# Konekt_Dash_Pro.net
KiCad netlist of a schematic drawn in EAGLE
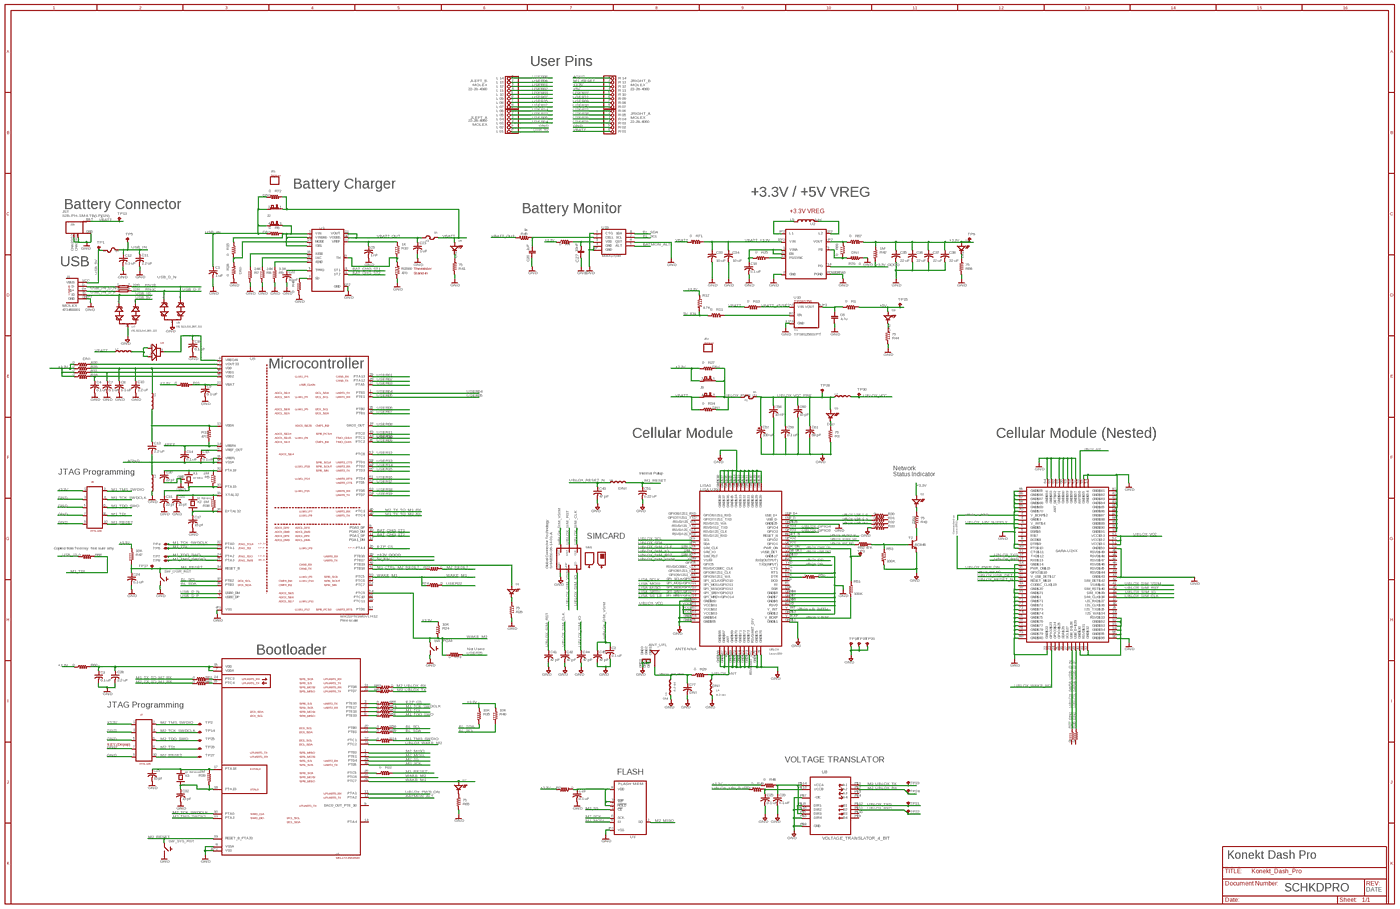
[diagram p0: schematic, sheet 1, overview]
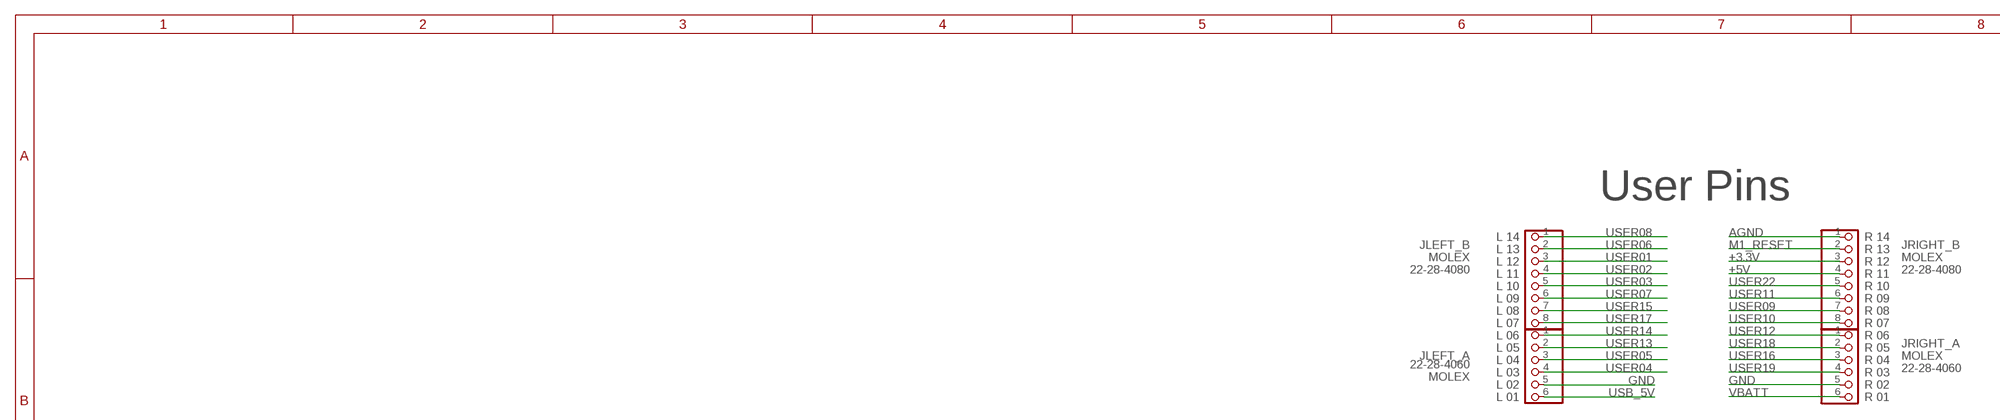
[diagram p1: schematic, sheet 1, part 1 of 4]
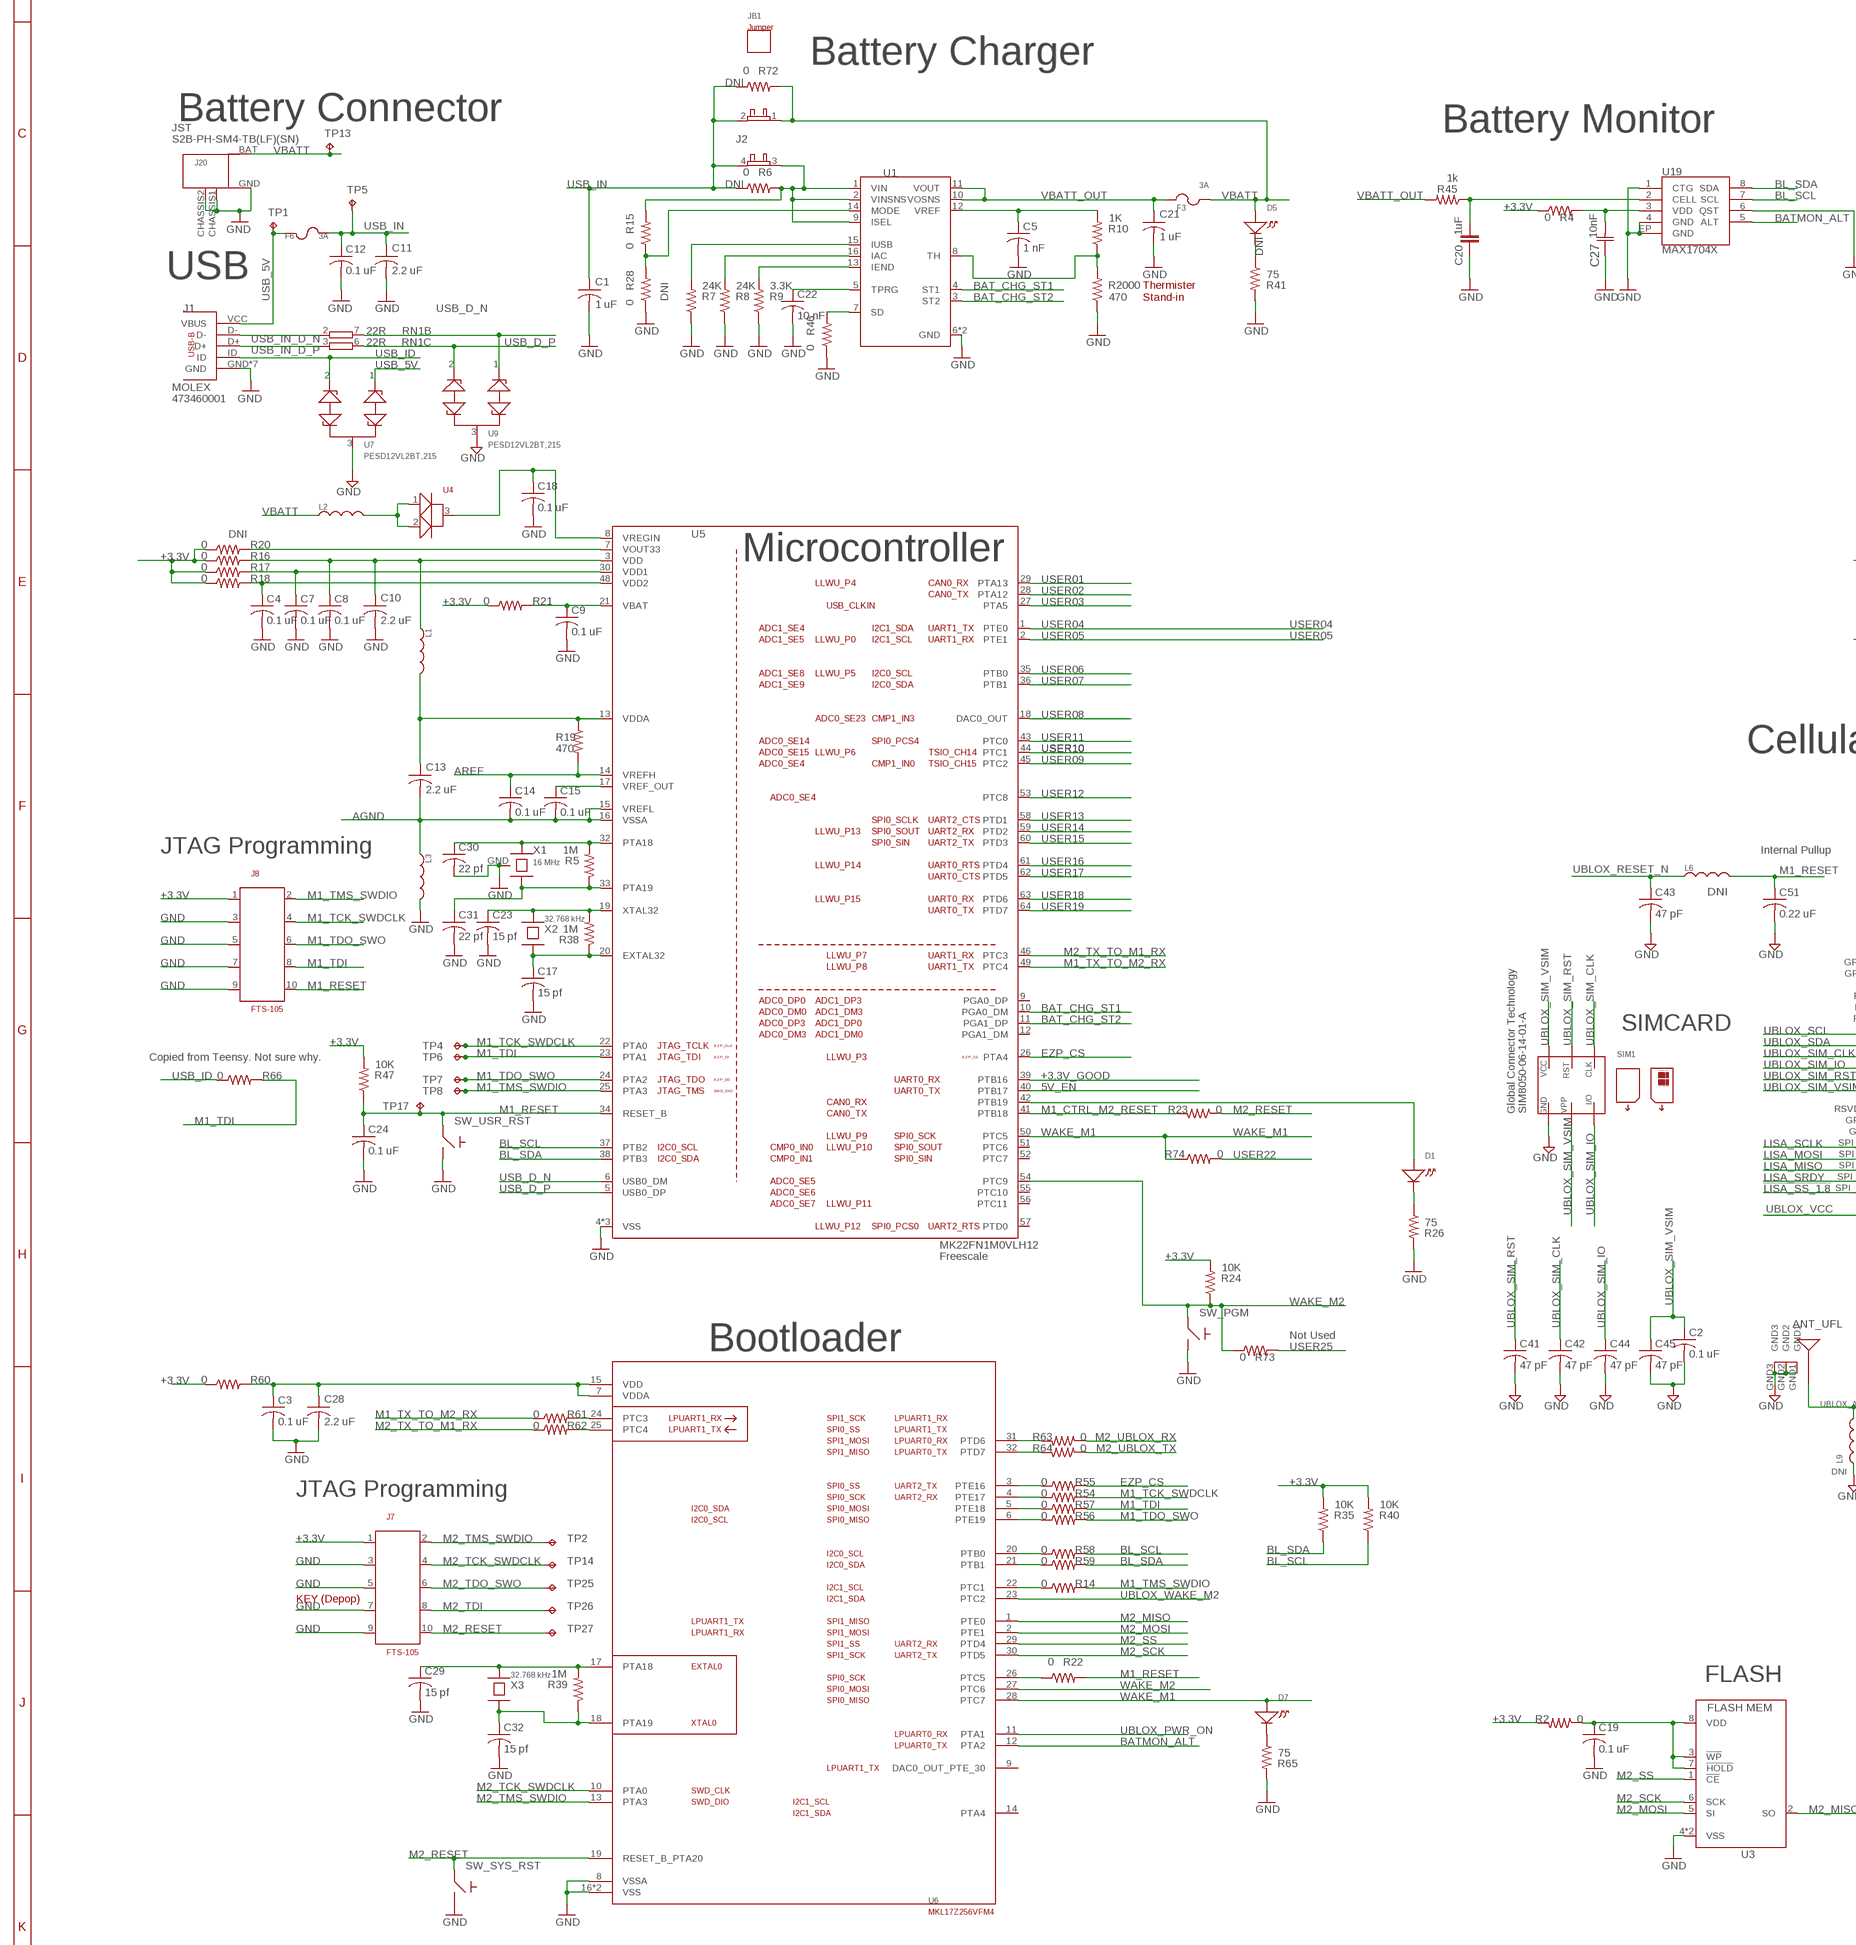
[diagram p2: schematic, sheet 1, part 2 of 4]
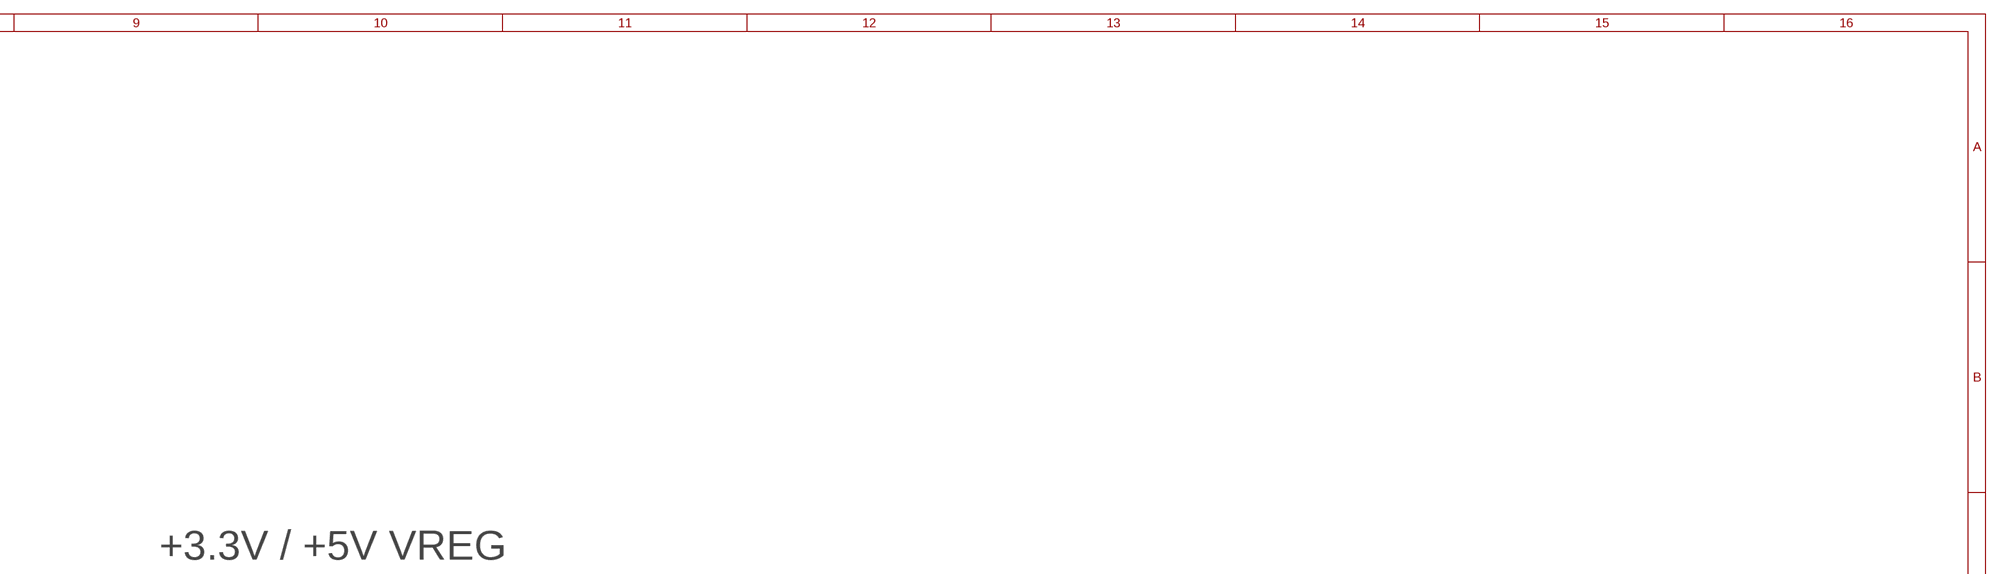
[diagram p3: schematic, sheet 1, part 3 of 4]
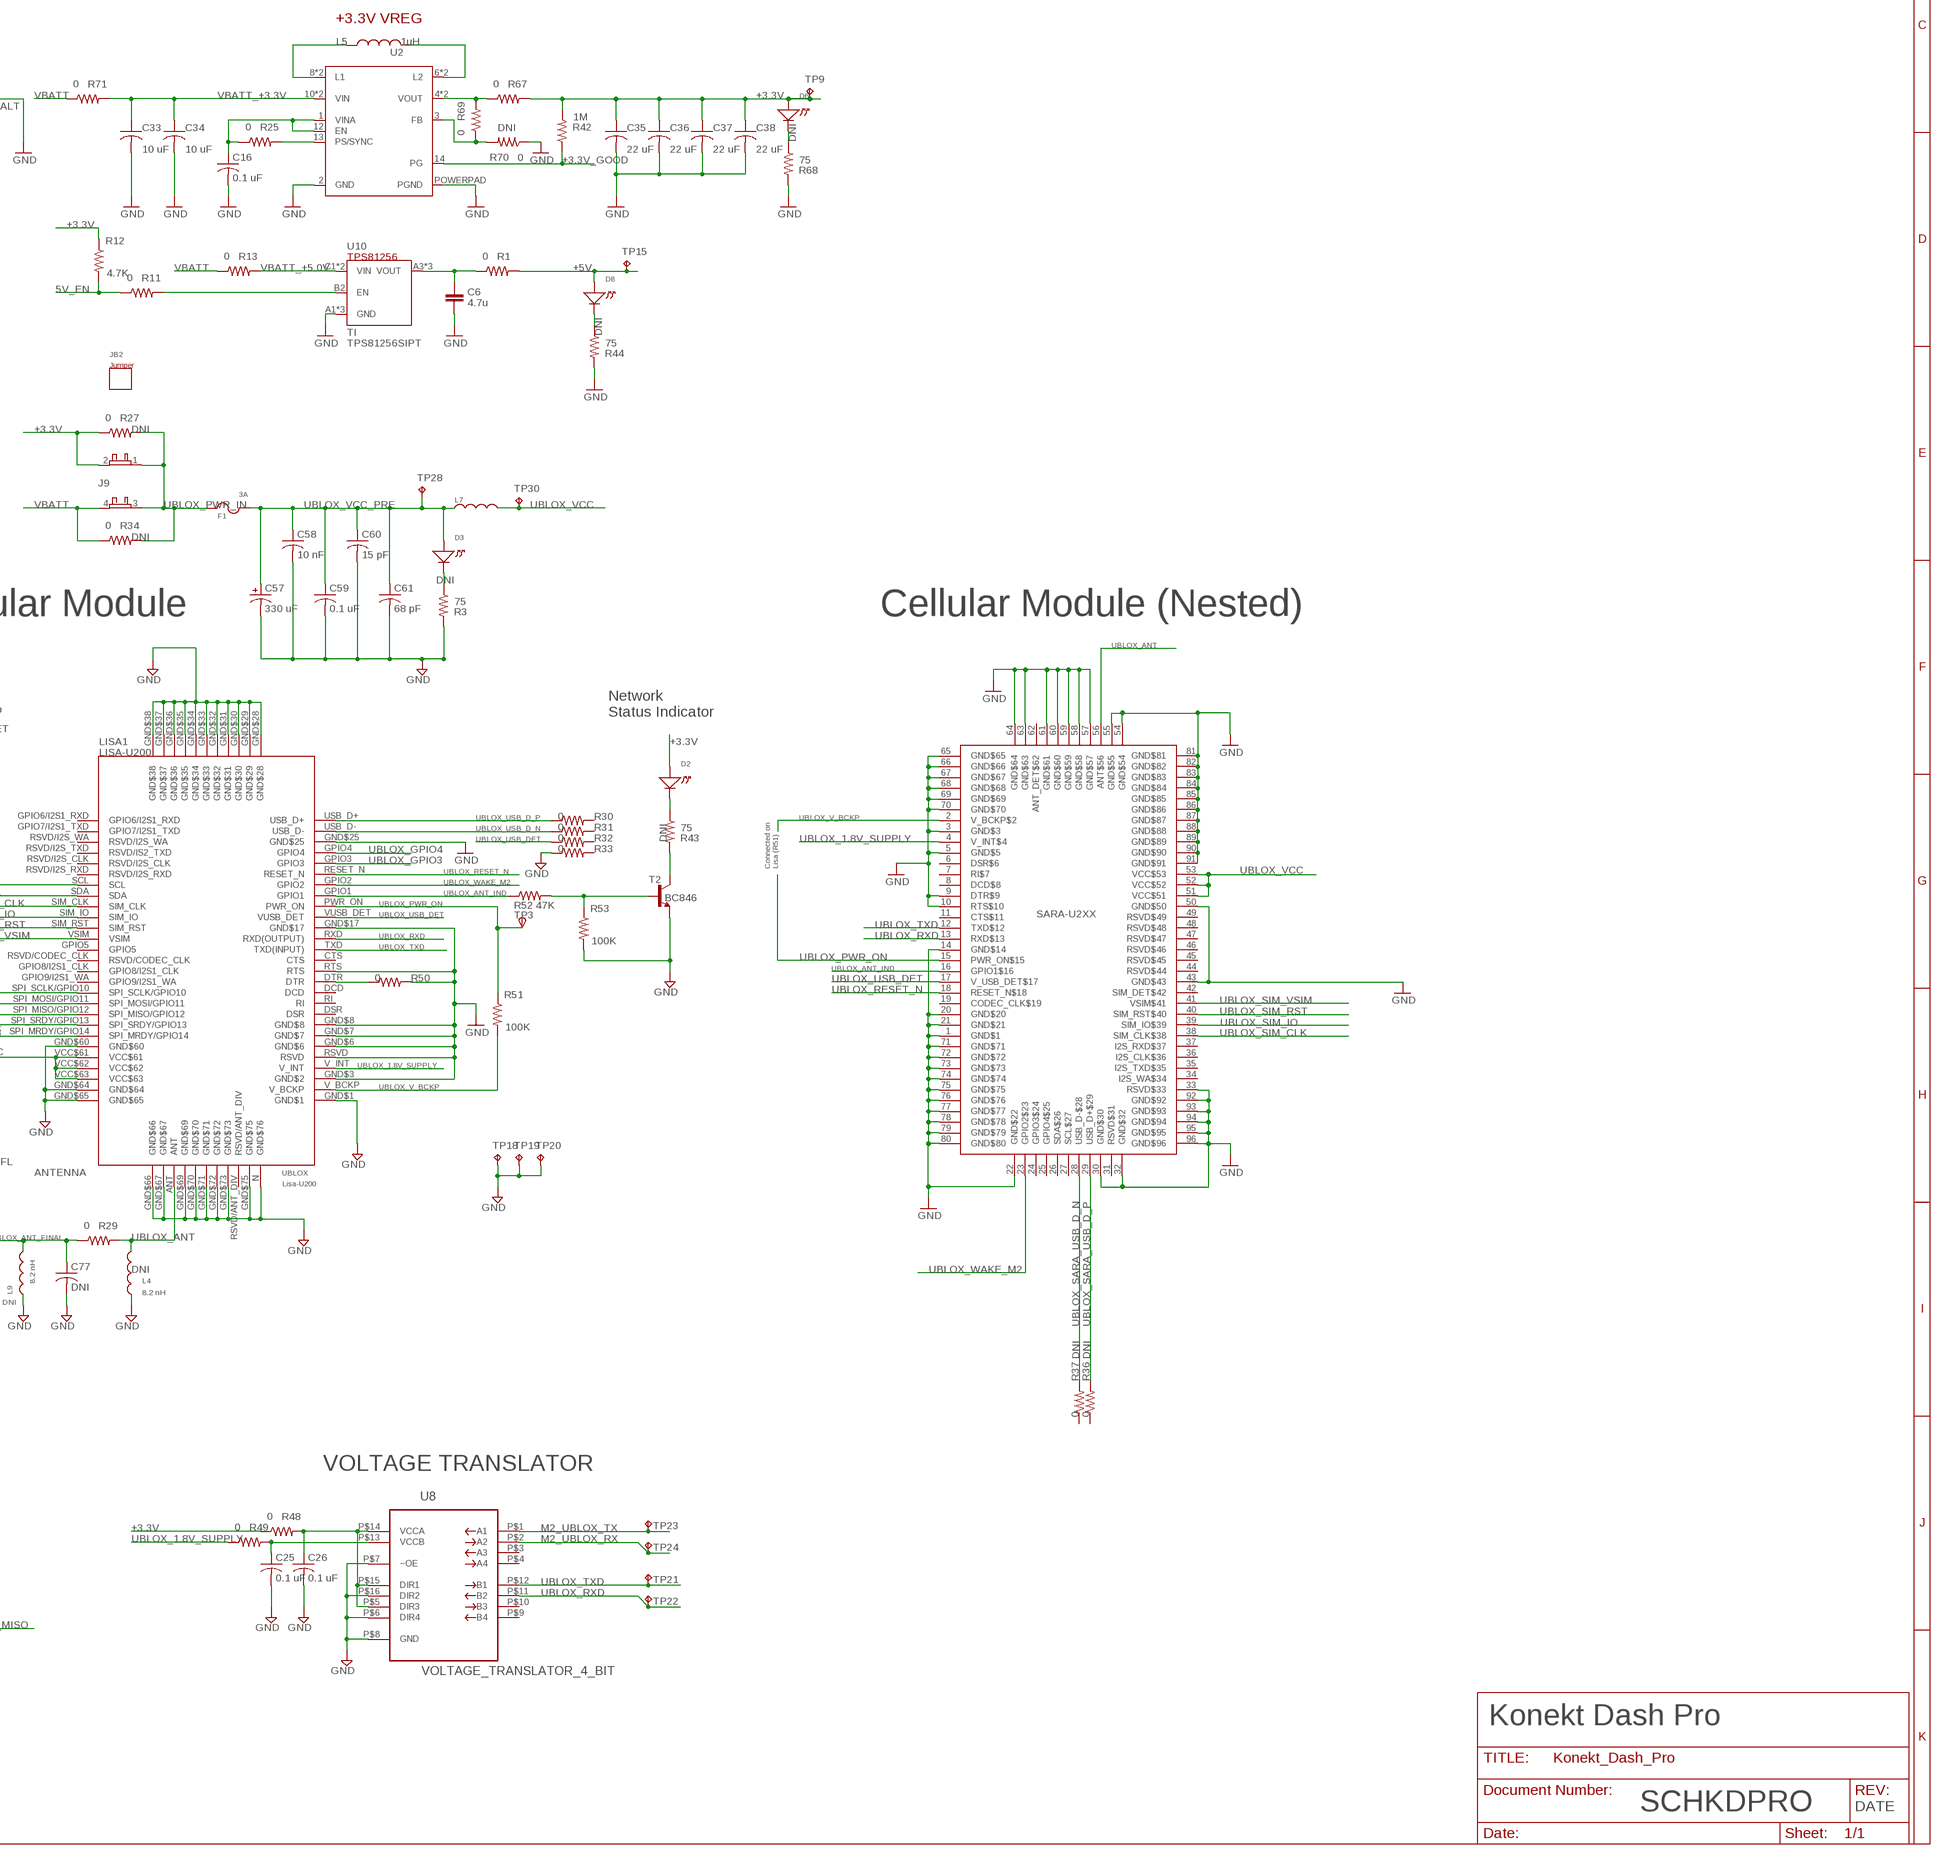
[diagram p4: schematic, sheet 1, part 4 of 4]

(export (version "E")
  (design (tool "Eeschema 10.0.6"))
  (components
    (comp (ref "ANT_UFL")
      (value "ANT-A-1JB")
      (footprint "eagle-import:UFL")
      (fields (field (name "MFG") "AMPHENOL") (field (name "PARTNUM") "A-1JB"))
      (libsource (lib "eagle-import") (part "ANT-A-1JB"))
    )
    (comp (ref "C1")
      (value "1 uF")
      (footprint "eagle-import:C0603")
      (fields (field (name "MFG") "MURATA") (field (name "MPN") "GRM188R71C105KA12D"))
      (libsource (lib "eagle-import") (part "resistor_C-USC0603"))
    )
    (comp (ref "C2")
      (value "0.1 uF")
      (footprint "eagle-import:C0402")
      (fields (field (name "MFG") "MURATA") (field (name "MPN") "GRM155R61C104KA88D"))
      (libsource (lib "eagle-import") (part "C-USC0402"))
    )
    (comp (ref "C3")
      (value "0.1 uF")
      (footprint "eagle-import:C0402")
      (fields (field (name "MFG") "MURATA") (field (name "MPN") "GRM155R61C104KA88D"))
      (libsource (lib "eagle-import") (part "C-USC0402"))
    )
    (comp (ref "C4")
      (value "0.1 uF")
      (footprint "eagle-import:C0402")
      (fields (field (name "MFG") "MURATA") (field (name "MPN") "GRM155R61C104KA88D"))
      (libsource (lib "eagle-import") (part "C-USC0402"))
    )
    (comp (ref "C5")
      (value "1 nF")
      (footprint "eagle-import:C0402")
      (fields (field (name "MFG") "MURATA") (field (name "MPN") "GRM319R71H102KA01D"))
      (libsource (lib "eagle-import") (part "resistor_C-USC0402"))
    )
    (comp (ref "C6")
      (value "4.7u")
      (footprint "eagle-import:C0603-ROUND")
      (fields (field (name "MFG") "MURATA") (field (name "MPN") "GRM188R61C475KAAJD"))
      (libsource (lib "eagle-import") (part "C-EU0603-RND"))
    )
    (comp (ref "C7")
      (value "0.1 uF")
      (footprint "eagle-import:C0402")
      (fields (field (name "MFG") "MURATA") (field (name "MPN") "GRM155R61C104KA88D"))
      (libsource (lib "eagle-import") (part "C-USC0402"))
    )
    (comp (ref "C8")
      (value "0.1 uF")
      (footprint "eagle-import:C0402")
      (fields (field (name "MFG") "MURATA") (field (name "MPN") "GRM155R61C104KA88D"))
      (libsource (lib "eagle-import") (part "C-USC0402"))
    )
    (comp (ref "C9")
      (value "0.1 uF")
      (footprint "eagle-import:C0402")
      (fields (field (name "MFG") "MURATA") (field (name "MPN") "GRM155R61C104KA88D"))
      (libsource (lib "eagle-import") (part "C-USC0402"))
    )
    (comp (ref "C10")
      (value "2.2 uF")
      (footprint "eagle-import:C0603")
      (fields (field (name "MFG") "SAMSUNG") (field (name "MPN") "CL10A225MQ8NNNC"))
      (libsource (lib "eagle-import") (part "resistor_C-USC0603"))
    )
    (comp (ref "C11")
      (value "2.2 uF")
      (footprint "eagle-import:C0603")
      (fields (field (name "MFG") "SAMSUNG") (field (name "MPN") "CL10A225MQ8NNNC"))
      (libsource (lib "eagle-import") (part "resistor_C-USC0603"))
    )
    (comp (ref "C12")
      (value "0.1 uF")
      (footprint "eagle-import:C0603")
      (fields (field (name "MFG") "AVX") (field (name "MPN") "0603YC104KAT2A"))
      (libsource (lib "eagle-import") (part "resistor_C-USC0603"))
    )
    (comp (ref "C13")
      (value "2.2 uF")
      (footprint "eagle-import:C0603")
      (fields (field (name "MFG") "SAMSUNG") (field (name "MPN") "CL10A225MQ8NNNC"))
      (libsource (lib "eagle-import") (part "resistor_C-USC0603"))
    )
    (comp (ref "C14")
      (value "0.1 uF")
      (footprint "eagle-import:C0402")
      (fields (field (name "MFG") "MURATA") (field (name "MPN") "GRM155R61C104KA88D"))
      (libsource (lib "eagle-import") (part "C-USC0402"))
    )
    (comp (ref "C15")
      (value "0.1 uF")
      (footprint "eagle-import:C0402")
      (fields (field (name "MFG") "AVX/ELCO") (field (name "MPN") "GRM155R61C104KA88D"))
      (libsource (lib "eagle-import") (part "C-USC0402"))
    )
    (comp (ref "C16")
      (value "0.1 uF")
      (footprint "eagle-import:C0603")
      (fields (field (name "MFG") "AVX") (field (name "MPN") "0603YC104KAT2A"))
      (libsource (lib "eagle-import") (part "resistor_C-USC0603"))
    )
    (comp (ref "C17")
      (value "15 pf")
      (footprint "eagle-import:C0402")
      (fields (field (name "MFG") "AVX/ELCO") (field (name "MPN") "04025A150JAT2A"))
      (libsource (lib "eagle-import") (part "C-USC0402"))
    )
    (comp (ref "C18")
      (value "0.1 uF")
      (footprint "eagle-import:C0402")
      (fields (field (name "MFG") "MURATA") (field (name "MPN") "GRM155R61C104KA88D"))
      (libsource (lib "eagle-import") (part "C-USC0402"))
    )
    (comp (ref "C19")
      (value "0.1 uF")
      (footprint "eagle-import:C0402")
      (fields (field (name "MFG") "MURATA") (field (name "MPN") "GRM155R61C104KA88D"))
      (libsource (lib "eagle-import") (part "C-USC0402"))
    )
    (comp (ref "C20")
      (value "1uF")
      (footprint "eagle-import:0402-CAP")
      (description "Capacitor, 10%, 50V")
      (fields
        (field (name "MFG") "AVX")
        (field (name "MPN") "04026D105KAT2A")
        (field (name "TOLERANCE") "10%")
        (field (name "VOLTAGE") "50V")
      )
      (libsource (lib "eagle-import") (part "CAPACITOR0402"))
    )
    (comp (ref "C21")
      (value "1 uF")
      (footprint "eagle-import:C0603")
      (fields (field (name "MFG") "MURATA") (field (name "MPN") "GRM188R71C105KA12D"))
      (libsource (lib "eagle-import") (part "resistor_C-USC0603"))
    )
    (comp (ref "C22")
      (value "10 nF")
      (footprint "eagle-import:C0402")
      (fields (field (name "MFG") "MURATA") (field (name "MPN") "GRM155R71C103KA01D"))
      (libsource (lib "eagle-import") (part "resistor_C-USC0402"))
    )
    (comp (ref "C23")
      (value "15 pf")
      (footprint "eagle-import:C0402")
      (fields (field (name "MFG") "AVX/ELCO") (field (name "MPN") "04025A150JAT2A"))
      (libsource (lib "eagle-import") (part "C-USC0402"))
    )
    (comp (ref "C24")
      (value "0.1 uF")
      (footprint "eagle-import:C0402")
      (fields (field (name "MFG") "MURATA") (field (name "MPN") "GRM155R61C104KA88D"))
      (libsource (lib "eagle-import") (part "C-USC0402"))
    )
    (comp (ref "C25")
      (value "0.1 uF")
      (footprint "eagle-import:C0402")
      (fields (field (name "MFG") "MURATA") (field (name "MPN") "GRM155R61C104KA88D"))
      (libsource (lib "eagle-import") (part "C-USC0402"))
    )
    (comp (ref "C26")
      (value "0.1 uF")
      (footprint "eagle-import:C0402")
      (fields (field (name "MFG") "MURATA") (field (name "MPN") "GRM155R61C104KA88D"))
      (libsource (lib "eagle-import") (part "C-USC0402"))
    )
    (comp (ref "C27")
      (value "10nF")
      (footprint "eagle-import:CAPC1005X60N")
      (description "CAPACITOR, 0402")
      (fields (field (name "MPN") "GRM155R71E103KA01D") (field (name "TOLERANCE") "±10%"))
      (libsource (lib "eagle-import") (part "GRM155R71E103KA01D"))
    )
    (comp (ref "C28")
      (value "2.2 uF")
      (footprint "eagle-import:C0603")
      (fields (field (name "MFG") "SAMSUNG") (field (name "MPN") "CL10A225MQ8NNNC"))
      (libsource (lib "eagle-import") (part "resistor_C-USC0603"))
    )
    (comp (ref "C29")
      (value "15 pf")
      (footprint "eagle-import:C0402")
      (fields (field (name "MFG") "AVX/ELCO") (field (name "MPN") "04025A150JAT2A"))
      (libsource (lib "eagle-import") (part "C-USC0402"))
    )
    (comp (ref "C30")
      (value "22 pf")
      (footprint "eagle-import:C0402")
      (fields (field (name "MFG") "AVX/ELCO") (field (name "MPN") "04025A220JAT2A"))
      (libsource (lib "eagle-import") (part "C-USC0402"))
    )
    (comp (ref "C31")
      (value "22 pf")
      (footprint "eagle-import:C0402")
      (fields (field (name "MFG") "AVX/ELCO") (field (name "MPN") "04025A220JAT2A"))
      (libsource (lib "eagle-import") (part "C-USC0402"))
    )
    (comp (ref "C32")
      (value "15 pf")
      (footprint "eagle-import:C0402")
      (fields (field (name "MFG") "AVX/ELCO") (field (name "MPN") "04025A150JAT2A"))
      (libsource (lib "eagle-import") (part "C-USC0402"))
    )
    (comp (ref "C33")
      (value "10 uF")
      (footprint "eagle-import:C0603")
      (fields (field (name "MFG") "MURATA") (field (name "MPN") "GRM188R60J106ME84D"))
      (libsource (lib "eagle-import") (part "resistor_C-USC0603"))
    )
    (comp (ref "C34")
      (value "10 uF")
      (footprint "eagle-import:C0603")
      (fields (field (name "MFG") "MURATA") (field (name "MPN") "GRM188R60J106ME84D"))
      (libsource (lib "eagle-import") (part "resistor_C-USC0603"))
    )
    (comp (ref "C35")
      (value "22 uF")
      (footprint "eagle-import:C0603")
      (fields (field (name "MFG") "MURATA") (field (name "MPN") "GRM188R60J226MEA0D"))
      (libsource (lib "eagle-import") (part "resistor_C-USC0603"))
    )
    (comp (ref "C36")
      (value "22 uF")
      (footprint "eagle-import:C0603")
      (fields (field (name "MFG") "MURATA") (field (name "MPN") "GRM188R60J226MEA0D"))
      (libsource (lib "eagle-import") (part "resistor_C-USC0603"))
    )
    (comp (ref "C37")
      (value "22 uF")
      (footprint "eagle-import:C0603")
      (fields (field (name "MFG") "MURATA") (field (name "MPN") "GRM188R60J226MEA0D"))
      (libsource (lib "eagle-import") (part "resistor_C-USC0603"))
    )
    (comp (ref "C38")
      (value "22 uF")
      (footprint "eagle-import:C0603")
      (fields (field (name "MFG") "MURATA") (field (name "MPN") "GRM188R60J226MEA0D"))
      (libsource (lib "eagle-import") (part "resistor_C-USC0603"))
    )
    (comp (ref "C41")
      (value "47 pF")
      (footprint "eagle-import:C0402")
      (fields (field (name "MFG") "AVX") (field (name "MPN") "04025A470JAT2A"))
      (libsource (lib "eagle-import") (part "resistor_C-USC0402"))
    )
    (comp (ref "C42")
      (value "47 pF")
      (footprint "eagle-import:C0402")
      (fields (field (name "MFG") "AVX") (field (name "MPN") "04025A470JAT2A"))
      (libsource (lib "eagle-import") (part "resistor_C-USC0402"))
    )
    (comp (ref "C43")
      (value "47 pF")
      (footprint "eagle-import:C0402")
      (fields (field (name "MFG") "AVX") (field (name "MPN") "04025A470JAT2A"))
      (libsource (lib "eagle-import") (part "resistor_C-USC0402"))
    )
    (comp (ref "C44")
      (value "47 pF")
      (footprint "eagle-import:C0402")
      (fields (field (name "MFG") "AVX") (field (name "MPN") "04025A470JAT2A"))
      (libsource (lib "eagle-import") (part "resistor_C-USC0402"))
    )
    (comp (ref "C45")
      (value "47 pF")
      (footprint "eagle-import:C0402")
      (fields (field (name "MFG") "AVX") (field (name "MPN") "04025A470JAT2A"))
      (libsource (lib "eagle-import") (part "resistor_C-USC0402"))
    )
    (comp (ref "C51")
      (value "0.22 uF")
      (footprint "eagle-import:C0603")
      (fields (field (name "MFG") "AVX") (field (name "MPN") "0603YC224KAT2A"))
      (libsource (lib "eagle-import") (part "resistor_C-USC0603"))
    )
    (comp (ref "C57")
      (value "330 uF")
      (footprint "eagle-import:CAP_SMD_SIZE_D")
      (fields (field (name "MFG") "KEMET") (field (name "MPN") "T520D337M006ATE045"))
      (libsource (lib "eagle-import") (part "CAP_SMD_D_SIZED"))
    )
    (comp (ref "C58")
      (value "10 nF")
      (footprint "eagle-import:C0402")
      (fields (field (name "MFG") "MURATA") (field (name "MPN") "GRM155R71C103KA01D"))
      (libsource (lib "eagle-import") (part "resistor_C-USC0402"))
    )
    (comp (ref "C59")
      (value "0.1 uF")
      (footprint "eagle-import:C0603")
      (fields (field (name "MFG") "AVX") (field (name "MPN") "0603YC104KAT2A"))
      (libsource (lib "eagle-import") (part "resistor_C-USC0603"))
    )
    (comp (ref "C60")
      (value "15 pF")
      (footprint "eagle-import:C0402")
      (fields (field (name "MFG") "NIC") (field (name "MPN") "NMC0402NPO150J50TRPF"))
      (libsource (lib "eagle-import") (part "resistor_C-USC0402"))
    )
    (comp (ref "C61")
      (value "68 pF")
      (footprint "eagle-import:C0402")
      (fields (field (name "MFG") "MURATA") (field (name "MPN") "GRM1555C1H680JA01D"))
      (libsource (lib "eagle-import") (part "resistor_C-USC0402"))
    )
    (comp (ref "C77")
      (value "DNI")
      (footprint "eagle-import:C0402")
      (fields (field (name "MFG") "AVX"))
      (libsource (lib "eagle-import") (part "resistor_C-USC0402"))
    )
    (comp (ref "D1")
      (value "LED_0402_VLMW")
      (footprint "eagle-import:LED_0402_VISHAY_VLMW")
      (fields (field (name "MFG") "VISHAY") (field (name "MPN") "VLMW1500-GS08"))
      (libsource (lib "eagle-import") (part "LED_0402_VLMW"))
    )
    (comp (ref "D2")
      (value "LED_0402_VLMW")
      (footprint "eagle-import:LED_0402_VISHAY_VLMW")
      (fields (field (name "MFG") "VISHAY") (field (name "MPN") "VLMW1500-GS08"))
      (libsource (lib "eagle-import") (part "LED_0402_VLMW"))
    )
    (comp (ref "D3")
      (value "LED_0402_VLMW")
      (footprint "eagle-import:LED_0402_VISHAY_VLMW")
      (fields (field (name "MFG") "VISHAY") (field (name "MPN") "VLMW1500-GS08"))
      (libsource (lib "eagle-import") (part "LED_0402_VLMW"))
    )
    (comp (ref "D5")
      (value "LED_0402_VLMW")
      (footprint "eagle-import:LED_0402_VISHAY_VLMW")
      (fields (field (name "MFG") "VISHAY") (field (name "MPN") "VLMW1500-GS08"))
      (libsource (lib "eagle-import") (part "LED_0402_VLMW"))
    )
    (comp (ref "D6")
      (value "LED_0402_VLMW")
      (footprint "eagle-import:LED_0402_VISHAY_VLMW")
      (fields (field (name "MFG") "VISHAY") (field (name "MPN") "VLMW1500-GS08"))
      (libsource (lib "eagle-import") (part "LED_0402_VLMW"))
    )
    (comp (ref "D7")
      (value "LED_0402_VLMW")
      (footprint "eagle-import:LED_0402_VISHAY_VLMW")
      (fields (field (name "MFG") "VISHAY") (field (name "MPN") "VLMW1500-GS08"))
      (libsource (lib "eagle-import") (part "LED_0402_VLMW"))
    )
    (comp (ref "D8")
      (value "LED_0402_VLMW")
      (footprint "eagle-import:LED_0402_VISHAY_VLMW")
      (fields (field (name "MFG") "VISHAY") (field (name "MPN") "VLMW1500-GS08"))
      (libsource (lib "eagle-import") (part "LED_0402_VLMW"))
    )
    (comp (ref "F1")
      (value "3A")
      (footprint "eagle-import:R0603")
      (fields (field (name "MFG") "Bourns") (field (name "MPN") "SF-0603S300-2"))
      (libsource (lib "eagle-import") (part "FUSE_0603"))
    )
    (comp (ref "F3")
      (value "3A")
      (footprint "eagle-import:R0603")
      (fields (field (name "MFG") "Bourns") (field (name "MPN") "SF-0603S300-2"))
      (libsource (lib "eagle-import") (part "FUSE_0603"))
    )
    (comp (ref "F6")
      (value "3A")
      (footprint "eagle-import:R0603")
      (fields (field (name "MFG") "Bourns") (field (name "MPN") "SF-0603S300-2"))
      (libsource (lib "eagle-import") (part "FUSE_0603"))
    )
    (comp (ref "J1")
      (value "USB_MICRO_B_MOLEX_473460001")
      (footprint "eagle-import:USB_MICRO_MOLEX_473460001")
      (fields
        (field (name "MFG") "MOLEX")
        (field (name "PARTNUM") "473460001")
        (field (name "MPN") "473460001")
      )
      (libsource (lib "eagle-import") (part "USB_MICRO_B_MOLEX_473460001"))
    )
    (comp (ref "J2")
      (value "CON_JUMPER_1.27_2X2")
      (footprint "eagle-import:FCI_CON_1.27_2X2")
      (fields (field (name "MFG") "FCI") (field (name "MPN") "20021121-00004C4LF"))
      (libsource (lib "eagle-import") (part "CON_JUMPER_1.27_2X2"))
    )
    (comp (ref "J7")
      (value "FTS-105")
      (footprint "eagle-import:FTS-105")
      (fields (field (name "MFG") "SAMTEC") (field (name "PARTNUM") "FTS-105-01-F-DV"))
      (libsource (lib "eagle-import") (part "FTS-105"))
    )
    (comp (ref "J8")
      (value "FTS-105")
      (footprint "eagle-import:FTS-105")
      (fields (field (name "MFG") "SAMTEC") (field (name "PARTNUM") "FTS-105-01-F-DV"))
      (libsource (lib "eagle-import") (part "FTS-105"))
    )
    (comp (ref "J9")
      (value "CON_JUMPER_1.27_2X2")
      (footprint "eagle-import:FCI_CON_1.27_2X2")
      (fields (field (name "MFG") "FCI") (field (name "MPN") "20021121-00004C4LF"))
      (libsource (lib "eagle-import") (part "CON_JUMPER_1.27_2X2"))
    )
    (comp (ref "J20")
      (value "BAT_TERM")
      (footprint "eagle-import:JST-PH-2")
      (fields
        (field (name "MFG") "JST")
        (field (name "PARTNUM") "S2B-PH-SM4-TB(LF)(SN)")
        (field (name "MFG_1") "JST")
        (field (name "MPN") "S2B-PH-SM4-TB(LF)(SN)")
        (field (name "PARTNUM_1") "S2B-PH-SM4-TB(LF)(SN)")
      )
      (libsource (lib "eagle-import") (part "BAT_TERM"))
    )
    (comp (ref "JB1")
      (value "JUMPER_1.27MM")
      (footprint "eagle-import:NOTHING")
      (fields (field (name "MFG") "HARWIN") (field (name "MPN") "M50-1920005"))
      (libsource (lib "eagle-import") (part "JUMPER_1.27MM"))
    )
    (comp (ref "JB2")
      (value "JUMPER_1.27MM")
      (footprint "eagle-import:NOTHING")
      (fields (field (name "MFG") "HARWIN") (field (name "MPN") "M50-1920005"))
      (libsource (lib "eagle-import") (part "JUMPER_1.27MM"))
    )
    (comp (ref "JLEFT_A")
      (value "PINHD-1X6")
      (footprint "eagle-import:1X06")
      (fields (field (name "MFG") "MOLEX") (field (name "MPN") "22-28-4060"))
      (libsource (lib "eagle-import") (part "PINHD-1X6"))
    )
    (comp (ref "JLEFT_B")
      (value "HEADER_0.1_IN_8_POS")
      (footprint "eagle-import:HEADER_0.1_8_POS")
      (fields
        (field (name "MFG") "Adam Tech")
        (field (name "MPN") "RS1-08-G-.561-A11596")
        (field (name "MFG_1") "MOLEX")
        (field (name "MPN_1") "22-28-4080")
      )
      (libsource (lib "eagle-import") (part "HEADER_0.1_IN_8_POS"))
    )
    (comp (ref "JRIGHT_A")
      (value "PINHD-1X6")
      (footprint "eagle-import:1X06")
      (fields (field (name "MFG") "MOLEX") (field (name "MPN") "22-28-4060"))
      (libsource (lib "eagle-import") (part "PINHD-1X6"))
    )
    (comp (ref "JRIGHT_B")
      (value "HEADER_0.1_IN_8_POS")
      (footprint "eagle-import:HEADER_0.1_8_POS")
      (fields
        (field (name "MFG") "Adam Tech")
        (field (name "MPN") "RS1-08-G-.561-A11596")
        (field (name "MFG_1") "MOLEX")
        (field (name "MPN_1") "22-28-4080")
      )
      (libsource (lib "eagle-import") (part "HEADER_0.1_IN_8_POS"))
    )
    (comp (ref "L1")
      (value "INDUCTOR_0603")
      (footprint "eagle-import:R0603$1")
      (fields (field (name "MFG") "Murata") (field (name "MPN") "BLM18AG121SN1D"))
      (libsource (lib "eagle-import") (part "INDUCTOR_0603"))
    )
    (comp (ref "L2")
      (value "INDUCTOR_0603")
      (footprint "eagle-import:R0603$1")
      (fields (field (name "MFG") "TDK") (field (name "MPN") "MPZ1608S221A"))
      (libsource (lib "eagle-import") (part "INDUCTOR_0603"))
    )
    (comp (ref "L3")
      (value "INDUCTOR_0603")
      (footprint "eagle-import:R0603$1")
      (fields (field (name "MFG") "Murata") (field (name "MPN") "BLM18AG121SN1D"))
      (libsource (lib "eagle-import") (part "INDUCTOR_0603"))
    )
    (comp (ref "L4")
      (value "INDUCTOR_0402")
      (footprint "eagle-import:R0402")
      (fields (field (name "MFG") "TDK") (field (name "MPN") "DNI") (field (name "VAL") "8.2 nH"))
      (libsource (lib "eagle-import") (part "INDUCTOR_0402"))
    )
    (comp (ref "L5")
      (value "1uH")
      (footprint "eagle-import:COILCRAFT_XFL4020")
      (fields (field (name "MFG") "COILCRAFT") (field (name "MPN") "XFL4020-102MEC"))
      (libsource (lib "eagle-import") (part "INDUCTOR_1UH_XFL4020-102MEC"))
    )
    (comp (ref "L6")
      (value "INDUCTOR_0603")
      (footprint "eagle-import:R0603$1")
      (fields (field (name "MFG") "TDK") (field (name "MPN") "DNI"))
      (libsource (lib "eagle-import") (part "INDUCTOR_0603"))
    )
    (comp (ref "L7")
      (value "INDUCTOR_0603")
      (footprint "eagle-import:R0603$1")
      (fields (field (name "MFG") "MURATA") (field (name "MPN") "BLM18EG221SN1D"))
      (libsource (lib "eagle-import") (part "INDUCTOR_0603"))
    )
    (comp (ref "L9")
      (value "INDUCTOR_0402")
      (footprint "eagle-import:R0402")
      (fields (field (name "MFG") "TDK") (field (name "MPN") "DNI") (field (name "VAL") "8.2 nH"))
      (libsource (lib "eagle-import") (part "INDUCTOR_0402"))
    )
    (comp (ref "LISA1")
      (value "LISA-U200")
      (footprint "eagle-import:76PIN_LCC")
      (fields
        (field (name "MFG") "UBLOX")
        (field (name "MPN") "LISA-U200-02S")
        (field (name "PARTNUM") "Lisa-U200")
      )
      (libsource (lib "eagle-import") (part "LISA-U200"))
    )
    (comp (ref "R1")
      (value "0")
      (footprint "eagle-import:0402-RES")
      (description "Resistor, 1%, 0.125W")
      (fields
        (field (name "MANUFACTURER") "Panasonic")
        (field (name "MFG") "PANASONIC")
        (field (name "MPN") "ERJ-2GE0R00X")
      )
      (libsource (lib "eagle-import") (part "RESISTOR0402-RES"))
    )
    (comp (ref "R2")
      (value "0")
      (footprint "eagle-import:0402-RES")
      (description "Resistor, 1%, 0.125W")
      (fields
        (field (name "MANUFACTURER") "Panasonic")
        (field (name "MFG") "PANASONIC")
        (field (name "MPN") "ERJ-2GE0R00X")
      )
      (libsource (lib "eagle-import") (part "RESISTOR0402-RES"))
    )
    (comp (ref "R3")
      (value "75")
      (footprint "eagle-import:0402-RES")
      (description "Resistor, 1%, 0.125W")
      (fields
        (field (name "MANUFACTURER") "Panasonic")
        (field (name "MFG") "PANASONIC")
        (field (name "MPN") "DNI")
      )
      (libsource (lib "eagle-import") (part "RESISTOR0402-RES"))
    )
    (comp (ref "R4")
      (value "0")
      (footprint "eagle-import:0402-RES")
      (description "Resistor, 1%, 0.125W")
      (fields
        (field (name "MANUFACTURER") "Panasonic")
        (field (name "MFG") "PANASONIC")
        (field (name "MPN") "ERJ-2GE0R00X")
      )
      (libsource (lib "eagle-import") (part "RESISTOR0402-RES"))
    )
    (comp (ref "R5")
      (value "1M")
      (footprint "eagle-import:0402-RES")
      (description "Resistor, 1%, 0.125W")
      (fields
        (field (name "MANUFACTURER") "Yaego")
        (field (name "MFG") "YAEGO")
        (field (name "MPN") "RC0402JR-071ML")
      )
      (libsource (lib "eagle-import") (part "RESISTOR0402-RES"))
    )
    (comp (ref "R6")
      (value "0")
      (footprint "eagle-import:0402-RES")
      (description "Resistor, 1%, 0.125W")
      (fields
        (field (name "MANUFACTURER") "Panasonic")
        (field (name "MFG") "PANASONIC")
        (field (name "MPN") "DNI")
      )
      (libsource (lib "eagle-import") (part "RESISTOR0402-RES"))
    )
    (comp (ref "R7")
      (value "24K")
      (footprint "eagle-import:0402-RES")
      (description "Resistor, 1%, 0.125W")
      (fields
        (field (name "MANUFACTURER") "Yaego")
        (field (name "MFG") "YAEGO")
        (field (name "MPN") "RC0402JR-0724KL")
      )
      (libsource (lib "eagle-import") (part "RESISTOR0402-RES"))
    )
    (comp (ref "R8")
      (value "24K")
      (footprint "eagle-import:0402-RES")
      (description "Resistor, 1%, 0.125W")
      (fields
        (field (name "MANUFACTURER") "Yaego")
        (field (name "MFG") "YAEGO")
        (field (name "MPN") "RC0402JR-0724KL")
      )
      (libsource (lib "eagle-import") (part "RESISTOR0402-RES"))
    )
    (comp (ref "R9")
      (value "3.3K")
      (footprint "eagle-import:0402-RES")
      (description "Resistor, 1%, 0.125W")
      (fields
        (field (name "MANUFACTURER") "Yaego")
        (field (name "MFG") "YAEGO")
        (field (name "MPN") "RC0402JR-073K3L")
      )
      (libsource (lib "eagle-import") (part "RESISTOR0402-RES"))
    )
    (comp (ref "R10")
      (value "1K")
      (footprint "eagle-import:0402-RES")
      (description "Resistor, 1%, 0.125W")
      (fields
        (field (name "MANUFACTURER") "Yaego")
        (field (name "MFG") "YAEGO")
        (field (name "MPN") "RC0402JR-071KL")
      )
      (libsource (lib "eagle-import") (part "RESISTOR0402-RES"))
    )
    (comp (ref "R11")
      (value "0")
      (footprint "eagle-import:0402-RES")
      (description "Resistor, 1%, 0.125W")
      (fields
        (field (name "MANUFACTURER") "Panasonic")
        (field (name "MFG") "PANASONIC")
        (field (name "MPN") "ERJ-2GE0R00X")
      )
      (libsource (lib "eagle-import") (part "RESISTOR0402-RES"))
    )
    (comp (ref "R12")
      (value "4.7K")
      (footprint "eagle-import:R0402")
      (fields (field (name "MFG") "Panasonic") (field (name "MPN") "ERJ-2GEJ472X"))
      (libsource (lib "eagle-import") (part "R-US_R0402"))
    )
    (comp (ref "R13")
      (value "0")
      (footprint "eagle-import:0402-RES")
      (description "Resistor, 1%, 0.125W")
      (fields
        (field (name "MANUFACTURER") "Panasonic")
        (field (name "MFG") "PANASONIC")
        (field (name "MPN") "ERJ-2GE0R00X")
      )
      (libsource (lib "eagle-import") (part "RESISTOR0402-RES"))
    )
    (comp (ref "R14")
      (value "0")
      (footprint "eagle-import:0402-RES")
      (description "Resistor, 1%, 0.125W")
      (fields
        (field (name "MANUFACTURER") "Panasonic")
        (field (name "MFG") "PANASONIC")
        (field (name "MPN") "ERJ-2GE0R00X")
      )
      (libsource (lib "eagle-import") (part "RESISTOR0402-RES"))
    )
    (comp (ref "R15")
      (value "0")
      (footprint "eagle-import:0402-RES")
      (description "Resistor, 1%, 0.125W")
      (fields
        (field (name "MANUFACTURER") "Panasonic")
        (field (name "MFG") "PANASONIC")
        (field (name "MPN") "ERJ-2GE0R00X")
      )
      (libsource (lib "eagle-import") (part "RESISTOR0402-RES"))
    )
    (comp (ref "R16")
      (value "0")
      (footprint "eagle-import:0402-RES")
      (description "Resistor, 1%, 0.125W")
      (fields
        (field (name "MANUFACTURER") "Panasonic")
        (field (name "MFG") "PANASONIC")
        (field (name "MPN") "ERJ-2GE0R00X")
      )
      (libsource (lib "eagle-import") (part "RESISTOR0402-RES"))
    )
    (comp (ref "R17")
      (value "0")
      (footprint "eagle-import:0402-RES")
      (description "Resistor, 1%, 0.125W")
      (fields
        (field (name "MANUFACTURER") "Panasonic")
        (field (name "MFG") "PANASONIC")
        (field (name "MPN") "ERJ-2GE0R00X")
      )
      (libsource (lib "eagle-import") (part "RESISTOR0402-RES"))
    )
    (comp (ref "R18")
      (value "0")
      (footprint "eagle-import:0402-RES")
      (description "Resistor, 1%, 0.125W")
      (fields
        (field (name "MANUFACTURER") "Panasonic")
        (field (name "MFG") "PANASONIC")
        (field (name "MPN") "ERJ-2GE0R00X")
      )
      (libsource (lib "eagle-import") (part "RESISTOR0402-RES"))
    )
    (comp (ref "R19")
      (value "470")
      (footprint "eagle-import:R0402")
      (fields (field (name "MFG") "Panasonic") (field (name "MPN") "ERJ-2GEJ471X"))
      (libsource (lib "eagle-import") (part "R-US_R0402"))
    )
    (comp (ref "R20")
      (value "0")
      (footprint "eagle-import:0402-RES")
      (description "Resistor, 1%, 0.125W")
      (fields
        (field (name "MANUFACTURER") "Panasonic")
        (field (name "MFG") "PANASONIC")
        (field (name "MPN") "DNI")
      )
      (libsource (lib "eagle-import") (part "RESISTOR0402-RES"))
    )
    (comp (ref "R21")
      (value "0")
      (footprint "eagle-import:0402-RES")
      (description "Resistor, 1%, 0.125W")
      (fields
        (field (name "MANUFACTURER") "Panasonic")
        (field (name "MFG") "PANASONIC")
        (field (name "MPN") "ERJ-2GE0R00X")
      )
      (libsource (lib "eagle-import") (part "RESISTOR0402-RES"))
    )
    (comp (ref "R22")
      (value "0")
      (footprint "eagle-import:0402-RES")
      (description "Resistor, 1%, 0.125W")
      (fields
        (field (name "MANUFACTURER") "Panasonic")
        (field (name "MFG") "PANASONIC")
        (field (name "MPN") "ERJ-2GE0R00X")
      )
      (libsource (lib "eagle-import") (part "RESISTOR0402-RES"))
    )
    (comp (ref "R23")
      (value "0")
      (footprint "eagle-import:0402-RES")
      (description "Resistor, 1%, 0.125W")
      (fields
        (field (name "MANUFACTURER") "Panasonic")
        (field (name "MFG") "PANASONIC")
        (field (name "MPN") "ERJ-2GE0R00X")
      )
      (libsource (lib "eagle-import") (part "RESISTOR0402-RES"))
    )
    (comp (ref "R24")
      (value "10K")
      (footprint "eagle-import:0402-RES")
      (description "Resistor, 1%, 0.125W")
      (fields
        (field (name "MANUFACTURER") "Yaego")
        (field (name "MFG") "YAEGO")
        (field (name "MPN") "RC0402JR-0710KL")
      )
      (libsource (lib "eagle-import") (part "RESISTOR0402-RES"))
    )
    (comp (ref "R25")
      (value "0")
      (footprint "eagle-import:0402-RES")
      (description "Resistor, 1%, 0.125W")
      (fields
        (field (name "MANUFACTURER") "Panasonic")
        (field (name "MFG") "PANASONIC")
        (field (name "MPN") "ERJ-2GE0R00X")
      )
      (libsource (lib "eagle-import") (part "RESISTOR0402-RES"))
    )
    (comp (ref "R26")
      (value "75")
      (footprint "eagle-import:0402-RES")
      (description "Resistor, 1%, 0.125W")
      (fields
        (field (name "MANUFACTURER") "Panasonic")
        (field (name "MFG") "PANASONIC")
        (field (name "MPN") "ERJ-2GEJ750X")
      )
      (libsource (lib "eagle-import") (part "RESISTOR0402-RES"))
    )
    (comp (ref "R27")
      (value "0")
      (footprint "eagle-import:0402-RES")
      (description "Resistor, 1%, 0.125W")
      (fields
        (field (name "MANUFACTURER") "Panasonic")
        (field (name "MFG") "PANASONIC")
        (field (name "MPN") "DNI")
      )
      (libsource (lib "eagle-import") (part "RESISTOR0402-RES"))
    )
    (comp (ref "R28")
      (value "0")
      (footprint "eagle-import:0402-RES")
      (description "Resistor, 1%, 0.125W")
      (fields
        (field (name "MANUFACTURER") "Panasonic")
        (field (name "MFG") "PANASONIC")
        (field (name "MPN") "DNI")
      )
      (libsource (lib "eagle-import") (part "RESISTOR0402-RES"))
    )
    (comp (ref "R29")
      (value "0")
      (footprint "eagle-import:0402-RES")
      (description "Resistor, 1%, 0.125W")
      (fields
        (field (name "MANUFACTURER") "Panasonic")
        (field (name "MFG") "PANASONIC")
        (field (name "MPN") "ERJ-2GE0R00X")
      )
      (libsource (lib "eagle-import") (part "RESISTOR0402-RES"))
    )
    (comp (ref "R30")
      (value "0")
      (footprint "eagle-import:0402-RES")
      (description "Resistor, 1%, 0.125W")
      (fields
        (field (name "MANUFACTURER") "Panasonic")
        (field (name "MFG") "PANASONIC")
        (field (name "MPN") "ERJ-2GE0R00X")
      )
      (libsource (lib "eagle-import") (part "RESISTOR0402-RES"))
    )
    (comp (ref "R31")
      (value "0")
      (footprint "eagle-import:0402-RES")
      (description "Resistor, 1%, 0.125W")
      (fields
        (field (name "MANUFACTURER") "Panasonic")
        (field (name "MFG") "PANASONIC")
        (field (name "MPN") "ERJ-2GE0R00X")
      )
      (libsource (lib "eagle-import") (part "RESISTOR0402-RES"))
    )
    (comp (ref "R32")
      (value "0")
      (footprint "eagle-import:0402-RES")
      (description "Resistor, 1%, 0.125W")
      (fields
        (field (name "MANUFACTURER") "Panasonic")
        (field (name "MFG") "PANASONIC")
        (field (name "MPN") "ERJ-2GE0R00X")
      )
      (libsource (lib "eagle-import") (part "RESISTOR0402-RES"))
    )
    (comp (ref "R33")
      (value "0")
      (footprint "eagle-import:0402-RES")
      (description "Resistor, 1%, 0.125W")
      (fields
        (field (name "MANUFACTURER") "Panasonic")
        (field (name "MFG") "PANASONIC")
        (field (name "MPN") "ERJ-2GE0R00X")
      )
      (libsource (lib "eagle-import") (part "RESISTOR0402-RES"))
    )
    (comp (ref "R34")
      (value "0")
      (footprint "eagle-import:0402-RES")
      (description "Resistor, 1%, 0.125W")
      (fields
        (field (name "MANUFACTURER") "Panasonic")
        (field (name "MFG") "PANASONIC")
        (field (name "MPN") "DNI")
      )
      (libsource (lib "eagle-import") (part "RESISTOR0402-RES"))
    )
    (comp (ref "R35")
      (value "10K")
      (footprint "eagle-import:0402-RES")
      (description "Resistor, 1%, 0.125W")
      (fields
        (field (name "MANUFACTURER") "Yaego")
        (field (name "MFG") "YAEGO")
        (field (name "MPN") "RC0402JR-0710KL")
      )
      (libsource (lib "eagle-import") (part "RESISTOR0402-RES"))
    )
    (comp (ref "R36")
      (value "0")
      (footprint "eagle-import:0402-RES")
      (description "Resistor, 1%, 0.125W")
      (fields
        (field (name "MANUFACTURER") "Panasonic")
        (field (name "MFG") "PANASONIC")
        (field (name "MPN") "DNI")
      )
      (libsource (lib "eagle-import") (part "RESISTOR0402-RES"))
    )
    (comp (ref "R37")
      (value "0")
      (footprint "eagle-import:0402-RES")
      (description "Resistor, 1%, 0.125W")
      (fields
        (field (name "MANUFACTURER") "Panasonic")
        (field (name "MFG") "PANASONIC")
        (field (name "MPN") "DNI")
      )
      (libsource (lib "eagle-import") (part "RESISTOR0402-RES"))
    )
    (comp (ref "R38")
      (value "1M")
      (footprint "eagle-import:0402-RES")
      (description "Resistor, 1%, 0.125W")
      (fields
        (field (name "MANUFACTURER") "Yaego")
        (field (name "MFG") "YAEGO")
        (field (name "MPN") "RC0402JR-071ML")
      )
      (libsource (lib "eagle-import") (part "RESISTOR0402-RES"))
    )
    (comp (ref "R39")
      (value "1M")
      (footprint "eagle-import:0402-RES")
      (description "Resistor, 1%, 0.125W")
      (fields
        (field (name "MANUFACTURER") "Yaego")
        (field (name "MFG") "YAEGO")
        (field (name "MPN") "RC0402JR-071ML")
      )
      (libsource (lib "eagle-import") (part "RESISTOR0402-RES"))
    )
    (comp (ref "R40")
      (value "10K")
      (footprint "eagle-import:0402-RES")
      (description "Resistor, 1%, 0.125W")
      (fields
        (field (name "MANUFACTURER") "Yaego")
        (field (name "MFG") "YAEGO")
        (field (name "MPN") "RC0402JR-0710KL")
      )
      (libsource (lib "eagle-import") (part "RESISTOR0402-RES"))
    )
    (comp (ref "R41")
      (value "75")
      (footprint "eagle-import:0402-RES")
      (description "Resistor, 1%, 0.125W")
      (fields
        (field (name "MANUFACTURER") "Panasonic")
        (field (name "MFG") "PANASONIC")
        (field (name "MPN") "DNI")
      )
      (libsource (lib "eagle-import") (part "RESISTOR0402-RES"))
    )
    (comp (ref "R42")
      (value "1M")
      (footprint "eagle-import:0402-RES")
      (description "Resistor, 1%, 0.125W")
      (fields
        (field (name "MANUFACTURER") "Yaego")
        (field (name "MFG") "YAEGO")
        (field (name "MPN") "RC0402JR-071ML")
      )
      (libsource (lib "eagle-import") (part "RESISTOR0402-RES"))
    )
    (comp (ref "R43")
      (value "75")
      (footprint "eagle-import:0402-RES")
      (description "Resistor, 1%, 0.125W")
      (fields
        (field (name "MANUFACTURER") "Panasonic")
        (field (name "MFG") "PANASONIC")
        (field (name "MPN") "DNI")
      )
      (libsource (lib "eagle-import") (part "RESISTOR0402-RES"))
    )
    (comp (ref "R44")
      (value "75")
      (footprint "eagle-import:0402-RES")
      (description "Resistor, 1%, 0.125W")
      (fields
        (field (name "MANUFACTURER") "Panasonic")
        (field (name "MFG") "PANASONIC")
        (field (name "MPN") "DNI")
      )
      (libsource (lib "eagle-import") (part "RESISTOR0402-RES"))
    )
    (comp (ref "R45")
      (value "1k")
      (footprint "eagle-import:0402-RES")
      (description "Resistor, 5%, 0.1W")
      (fields
        (field (name "MFG") "YAEGO")
        (field (name "MPN") "RC0402JR-071KL")
        (field (name "POWER") "0.1W")
        (field (name "TOLERANCE") "5%")
      )
      (libsource (lib "eagle-import") (part "RESISTOR"))
    )
    (comp (ref "R46")
      (value "0")
      (footprint "eagle-import:0402-RES")
      (description "Resistor, 1%, 0.125W")
      (fields
        (field (name "MANUFACTURER") "Panasonic")
        (field (name "MFG") "PANASONIC")
        (field (name "MPN") "ERJ-2GE0R00X")
      )
      (libsource (lib "eagle-import") (part "RESISTOR0402-RES"))
    )
    (comp (ref "R47")
      (value "10K")
      (footprint "eagle-import:0402-RES")
      (description "Resistor, 1%, 0.125W")
      (fields
        (field (name "MANUFACTURER") "Yaego")
        (field (name "MFG") "YAEGO")
        (field (name "MPN") "RC0402JR-0710KL")
      )
      (libsource (lib "eagle-import") (part "RESISTOR0402-RES"))
    )
    (comp (ref "R48")
      (value "0")
      (footprint "eagle-import:0402-RES")
      (description "Resistor, 1%, 0.125W")
      (fields
        (field (name "MANUFACTURER") "Panasonic")
        (field (name "MFG") "PANASONIC")
        (field (name "MPN") "ERJ-2GE0R00X")
      )
      (libsource (lib "eagle-import") (part "RESISTOR0402-RES"))
    )
    (comp (ref "R49")
      (value "0")
      (footprint "eagle-import:0402-RES")
      (description "Resistor, 1%, 0.125W")
      (fields
        (field (name "MANUFACTURER") "Panasonic")
        (field (name "MFG") "PANASONIC")
        (field (name "MPN") "ERJ-2GE0R00X")
      )
      (libsource (lib "eagle-import") (part "RESISTOR0402-RES"))
    )
    (comp (ref "R50")
      (value "0")
      (footprint "eagle-import:0402-RES")
      (description "Resistor, 1%, 0.125W")
      (fields
        (field (name "MANUFACTURER") "Panasonic")
        (field (name "MFG") "PANASONIC")
        (field (name "MPN") "ERJ-2GE0R00X")
      )
      (libsource (lib "eagle-import") (part "RESISTOR0402-RES"))
    )
    (comp (ref "R51")
      (value "100K")
      (footprint "eagle-import:R0402")
      (fields (field (name "MFG") "Panasonic") (field (name "MPN") "ERJ-2GEJ104X"))
      (libsource (lib "eagle-import") (part "R-US_R0402"))
    )
    (comp (ref "R52")
      (value "47K")
      (footprint "eagle-import:R0402")
      (fields (field (name "MFG") "Panasonic") (field (name "MPN") "ERJ-2GEJ473X"))
      (libsource (lib "eagle-import") (part "R-US_R0402"))
    )
    (comp (ref "R53")
      (value "100K")
      (footprint "eagle-import:R0402")
      (fields (field (name "MFG") "Panasonic") (field (name "MPN") "ERJ-2GEJ104X"))
      (libsource (lib "eagle-import") (part "R-US_R0402"))
    )
    (comp (ref "R54")
      (value "0")
      (footprint "eagle-import:0402-RES")
      (description "Resistor, 1%, 0.125W")
      (fields
        (field (name "MANUFACTURER") "Panasonic")
        (field (name "MFG") "PANASONIC")
        (field (name "MPN") "ERJ-2GE0R00X")
      )
      (libsource (lib "eagle-import") (part "RESISTOR0402-RES"))
    )
    (comp (ref "R55")
      (value "0")
      (footprint "eagle-import:0402-RES")
      (description "Resistor, 1%, 0.125W")
      (fields
        (field (name "MANUFACTURER") "Panasonic")
        (field (name "MFG") "PANASONIC")
        (field (name "MPN") "ERJ-2GE0R00X")
      )
      (libsource (lib "eagle-import") (part "RESISTOR0402-RES"))
    )
    (comp (ref "R56")
      (value "0")
      (footprint "eagle-import:0402-RES")
      (description "Resistor, 1%, 0.125W")
      (fields
        (field (name "MANUFACTURER") "Panasonic")
        (field (name "MFG") "PANASONIC")
        (field (name "MPN") "ERJ-2GE0R00X")
      )
      (libsource (lib "eagle-import") (part "RESISTOR0402-RES"))
    )
    (comp (ref "R57")
      (value "0")
      (footprint "eagle-import:0402-RES")
      (description "Resistor, 1%, 0.125W")
      (fields
        (field (name "MANUFACTURER") "Panasonic")
        (field (name "MFG") "PANASONIC")
        (field (name "MPN") "ERJ-2GE0R00X")
      )
      (libsource (lib "eagle-import") (part "RESISTOR0402-RES"))
    )
    (comp (ref "R58")
      (value "0")
      (footprint "eagle-import:0402-RES")
      (description "Resistor, 1%, 0.125W")
      (fields
        (field (name "MANUFACTURER") "Panasonic")
        (field (name "MFG") "PANASONIC")
        (field (name "MPN") "ERJ-2GE0R00X")
      )
      (libsource (lib "eagle-import") (part "RESISTOR0402-RES"))
    )
    (comp (ref "R59")
      (value "0")
      (footprint "eagle-import:0402-RES")
      (description "Resistor, 1%, 0.125W")
      (fields
        (field (name "MANUFACTURER") "Panasonic")
        (field (name "MFG") "PANASONIC")
        (field (name "MPN") "ERJ-2GE0R00X")
      )
      (libsource (lib "eagle-import") (part "RESISTOR0402-RES"))
    )
    (comp (ref "R60")
      (value "0")
      (footprint "eagle-import:0402-RES")
      (description "Resistor, 1%, 0.125W")
      (fields
        (field (name "MANUFACTURER") "Panasonic")
        (field (name "MFG") "PANASONIC")
        (field (name "MPN") "ERJ-2GE0R00X")
      )
      (libsource (lib "eagle-import") (part "RESISTOR0402-RES"))
    )
    (comp (ref "R61")
      (value "0")
      (footprint "eagle-import:0402-RES")
      (description "Resistor, 1%, 0.125W")
      (fields
        (field (name "MANUFACTURER") "Panasonic")
        (field (name "MFG") "PANASONIC")
        (field (name "MPN") "ERJ-2GE0R00X")
      )
      (libsource (lib "eagle-import") (part "RESISTOR0402-RES"))
    )
    (comp (ref "R62")
      (value "0")
      (footprint "eagle-import:0402-RES")
      (description "Resistor, 1%, 0.125W")
      (fields
        (field (name "MANUFACTURER") "Panasonic")
        (field (name "MFG") "PANASONIC")
        (field (name "MPN") "ERJ-2GE0R00X")
      )
      (libsource (lib "eagle-import") (part "RESISTOR0402-RES"))
    )
    (comp (ref "R63")
      (value "0")
      (footprint "eagle-import:0402-RES")
      (description "Resistor, 1%, 0.125W")
      (fields
        (field (name "MANUFACTURER") "Panasonic")
        (field (name "MFG") "PANASONIC")
        (field (name "MPN") "ERJ-2GE0R00X")
      )
      (libsource (lib "eagle-import") (part "RESISTOR0402-RES"))
    )
    (comp (ref "R64")
      (value "0")
      (footprint "eagle-import:0402-RES")
      (description "Resistor, 1%, 0.125W")
      (fields
        (field (name "MANUFACTURER") "Panasonic")
        (field (name "MFG") "PANASONIC")
        (field (name "MPN") "ERJ-2GE0R00X")
      )
      (libsource (lib "eagle-import") (part "RESISTOR0402-RES"))
    )
    (comp (ref "R65")
      (value "75")
      (footprint "eagle-import:0402-RES")
      (description "Resistor, 1%, 0.125W")
      (fields
        (field (name "MANUFACTURER") "Panasonic")
        (field (name "MFG") "PANASONIC")
        (field (name "MPN") "ERJ-2GEJ750X")
      )
      (libsource (lib "eagle-import") (part "RESISTOR0402-RES"))
    )
    (comp (ref "R66")
      (value "0")
      (footprint "eagle-import:0402-RES")
      (description "Resistor, 1%, 0.125W")
      (fields
        (field (name "MANUFACTURER") "Panasonic")
        (field (name "MFG") "PANASONIC")
        (field (name "MPN") "ERJ-2GE0R00X")
      )
      (libsource (lib "eagle-import") (part "RESISTOR0402-RES"))
    )
    (comp (ref "R67")
      (value "0")
      (footprint "eagle-import:0402-RES")
      (description "Resistor, 1%, 0.125W")
      (fields
        (field (name "MANUFACTURER") "Panasonic")
        (field (name "MFG") "PANASONIC")
        (field (name "MPN") "ERJ-2GE0R00X")
      )
      (libsource (lib "eagle-import") (part "RESISTOR0402-RES"))
    )
    (comp (ref "R68")
      (value "75")
      (footprint "eagle-import:0402-RES")
      (description "Resistor, 1%, 0.125W")
      (fields
        (field (name "MANUFACTURER") "Panasonic")
        (field (name "MFG") "PANASONIC")
        (field (name "MPN") "DNI")
      )
      (libsource (lib "eagle-import") (part "RESISTOR0402-RES"))
    )
    (comp (ref "R69")
      (value "0")
      (footprint "eagle-import:0402-RES")
      (description "Resistor, 1%, 0.125W")
      (fields
        (field (name "MANUFACTURER") "Panasonic")
        (field (name "MFG") "PANASONIC")
        (field (name "MPN") "ERJ-2GE0R00X")
      )
      (libsource (lib "eagle-import") (part "RESISTOR0402-RES"))
    )
    (comp (ref "R70")
      (value "0")
      (footprint "eagle-import:0402-RES")
      (description "Resistor, 1%, 0.125W")
      (fields
        (field (name "MANUFACTURER") "Panasonic")
        (field (name "MFG") "PANASONIC")
        (field (name "MPN") "DNI")
      )
      (libsource (lib "eagle-import") (part "RESISTOR0402-RES"))
    )
    (comp (ref "R71")
      (value "0")
      (footprint "eagle-import:0402-RES")
      (description "Resistor, 1%, 0.125W")
      (fields
        (field (name "MANUFACTURER") "Panasonic")
        (field (name "MFG") "PANASONIC")
        (field (name "MPN") "ERJ-2GE0R00X")
      )
      (libsource (lib "eagle-import") (part "RESISTOR0402-RES"))
    )
    (comp (ref "R72")
      (value "0")
      (footprint "eagle-import:0402-RES")
      (description "Resistor, 1%, 0.125W")
      (fields
        (field (name "MANUFACTURER") "Panasonic")
        (field (name "MFG") "PANASONIC")
        (field (name "MPN") "DNI")
      )
      (libsource (lib "eagle-import") (part "RESISTOR0402-RES"))
    )
    (comp (ref "R73")
      (value "0")
      (footprint "eagle-import:0402-RES")
      (description "Resistor, 1%, 0.125W")
      (fields
        (field (name "MANUFACTURER") "Panasonic")
        (field (name "MFG") "PANASONIC")
        (field (name "MPN") "ERJ-2GE0R00X")
      )
      (libsource (lib "eagle-import") (part "RESISTOR0402-RES"))
    )
    (comp (ref "R74")
      (value "0")
      (footprint "eagle-import:0402-RES")
      (description "Resistor, 1%, 0.125W")
      (fields
        (field (name "MANUFACTURER") "Panasonic")
        (field (name "MFG") "PANASONIC")
        (field (name "MPN") "ERJ-2GE0R00X")
      )
      (libsource (lib "eagle-import") (part "RESISTOR0402-RES"))
    )
    (comp (ref "R2000")
      (value "470")
      (footprint "eagle-import:0402-RES")
      (description "Resistor, 1%, 0.125W")
      (fields
        (field (name "MANUFACTURER") "Yaego")
        (field (name "MFG") "YAEGO")
        (field (name "MPN") "RC0402JR-07470RL")
      )
      (libsource (lib "eagle-import") (part "RESISTOR0402-RES"))
    )
    (comp (ref "RN1")
      (value "22R")
      (footprint "eagle-import:CAY16")
      (fields
        (field (name "MFG") "BOURNES")
        (field (name "MPN") "CAY16-220J4LF")
        (field (name "PACKAGE") "CAY16")
        (field (name "PARTNUM") "CAY16-220J4LF")
      )
      (libsource (lib "eagle-import") (part "4R-NCAY16"))
    )
    (comp (ref "SARA1")
      (value "SARA-U2XX")
      (footprint "eagle-import:91-PIN_LGA")
      (fields
        (field (name "MFG") "U-BLOX")
        (field (name "PARTNUMBER") "SARA-U270")
        (field (name "MPN") "DNI")
        (field (name "PARTNUMBER_1") "SARA-U260")
      )
      (libsource (lib "eagle-import") (part "SARA-U2XX"))
    )
    (comp (ref "SIM1")
      (value "SIM_CARD_NANO_GLOBAL_CONNECTOR_TEC_SIM8050-6-0-14-01-A")
      (footprint "eagle-import:SIM_CARD_NANO")
      (fields (field (name "MFG") "Global Connector Technology") (field (name "MPN") "SIM8050-06-14-01-A"))
      (libsource (lib "eagle-import") (part "SIM_CARD_NANO_GLOBAL_CONNECTOR_TEC_SIM8050-6-0-14-01-A"))
    )
    (comp (ref "SW_PGM")
      (value "SWITCH_PANASONIC_EVP-BB2A1B000")
      (footprint "eagle-import:SWITCH_PANASONIC_EVPBB")
      (fields (field (name "MFG") "PANASONIC") (field (name "MPN") "EVP-BB2A1B000"))
      (libsource (lib "eagle-import") (part "SWITCH_PANASONIC_EVP-BB2A1B000"))
    )
    (comp (ref "SW_SYS_RST")
      (value "SWITCH_PANASONIC_EVP-BB2A1B000")
      (footprint "eagle-import:SWITCH_PANASONIC_EVPBB")
      (fields (field (name "MFG") "PANASONIC") (field (name "MPN") "EVP-BB2A1B000"))
      (libsource (lib "eagle-import") (part "SWITCH_PANASONIC_EVP-BB2A1B000"))
    )
    (comp (ref "SW_USR_RST")
      (value "SWITCH_PANASONIC_EVP-BB2A1B000")
      (footprint "eagle-import:SWITCH_PANASONIC_EVPBB")
      (fields (field (name "MFG") "PANASONIC") (field (name "MPN") "EVP-BB2A1B000"))
      (libsource (lib "eagle-import") (part "SWITCH_PANASONIC_EVP-BB2A1B000"))
    )
    (comp (ref "T2")
      (value "BC846")
      (footprint "eagle-import:SOT23")
      (fields (field (name "MFG") "ON SEMI") (field (name "MPN") "BC846ALT1G"))
      (libsource (lib "eagle-import") (part "BC846"))
    )
    (comp (ref "TP1")
      (value "TPTP08R")
      (footprint "eagle-import:TP08R")
      (libsource (lib "eagle-import") (part "TPTP08R"))
    )
    (comp (ref "TP2")
      (value "TPTP08R")
      (footprint "eagle-import:TP08R")
      (libsource (lib "eagle-import") (part "TPTP08R"))
    )
    (comp (ref "TP3")
      (value "TPSTP09R")
      (footprint "eagle-import:TP09R")
      (libsource (lib "eagle-import") (part "TPSTP09R"))
    )
    (comp (ref "TP4")
      (value "TPTP08R")
      (footprint "eagle-import:TP08R")
      (libsource (lib "eagle-import") (part "TPTP08R"))
    )
    (comp (ref "TP5")
      (value "TPTP08R")
      (footprint "eagle-import:TP08R")
      (libsource (lib "eagle-import") (part "TPTP08R"))
    )
    (comp (ref "TP6")
      (value "TPTP08R")
      (footprint "eagle-import:TP08R")
      (libsource (lib "eagle-import") (part "TPTP08R"))
    )
    (comp (ref "TP7")
      (value "TPTP08R")
      (footprint "eagle-import:TP08R")
      (libsource (lib "eagle-import") (part "TPTP08R"))
    )
    (comp (ref "TP8")
      (value "TPTP08R")
      (footprint "eagle-import:TP08R")
      (libsource (lib "eagle-import") (part "TPTP08R"))
    )
    (comp (ref "TP9")
      (value "TPTP08R")
      (footprint "eagle-import:TP08R")
      (libsource (lib "eagle-import") (part "TPTP08R"))
    )
    (comp (ref "TP13")
      (value "TPTP08R")
      (footprint "eagle-import:TP08R")
      (libsource (lib "eagle-import") (part "TPTP08R"))
    )
    (comp (ref "TP14")
      (value "TPTP08R")
      (footprint "eagle-import:TP08R")
      (libsource (lib "eagle-import") (part "TPTP08R"))
    )
    (comp (ref "TP15")
      (value "TPTP08R")
      (footprint "eagle-import:TP08R")
      (libsource (lib "eagle-import") (part "TPTP08R"))
    )
    (comp (ref "TP17")
      (value "TPTP08R")
      (footprint "eagle-import:TP08R")
      (libsource (lib "eagle-import") (part "TPTP08R"))
    )
    (comp (ref "TP18")
      (value "TPTP08R")
      (footprint "eagle-import:TP08R")
      (libsource (lib "eagle-import") (part "TPTP08R"))
    )
    (comp (ref "TP19")
      (value "TPTP08R")
      (footprint "eagle-import:TP08R")
      (libsource (lib "eagle-import") (part "TPTP08R"))
    )
    (comp (ref "TP20")
      (value "TPTP08R")
      (footprint "eagle-import:TP08R")
      (libsource (lib "eagle-import") (part "TPTP08R"))
    )
    (comp (ref "TP21")
      (value "TPTP08R")
      (footprint "eagle-import:TP08R")
      (libsource (lib "eagle-import") (part "TPTP08R"))
    )
    (comp (ref "TP22")
      (value "TPTP08R")
      (footprint "eagle-import:TP08R")
      (libsource (lib "eagle-import") (part "TPTP08R"))
    )
    (comp (ref "TP23")
      (value "TPTP08R")
      (footprint "eagle-import:TP08R")
      (libsource (lib "eagle-import") (part "TPTP08R"))
    )
    (comp (ref "TP24")
      (value "TPTP08R")
      (footprint "eagle-import:TP08R")
      (libsource (lib "eagle-import") (part "TPTP08R"))
    )
    (comp (ref "TP25")
      (value "TPTP08R")
      (footprint "eagle-import:TP08R")
      (libsource (lib "eagle-import") (part "TPTP08R"))
    )
    (comp (ref "TP26")
      (value "TPTP08R")
      (footprint "eagle-import:TP08R")
      (libsource (lib "eagle-import") (part "TPTP08R"))
    )
    (comp (ref "TP27")
      (value "TPTP08R")
      (footprint "eagle-import:TP08R")
      (libsource (lib "eagle-import") (part "TPTP08R"))
    )
    (comp (ref "TP28")
      (value "TPTP08R")
      (footprint "eagle-import:TP08R")
      (libsource (lib "eagle-import") (part "TPTP08R"))
    )
    (comp (ref "TP30")
      (value "TPTP08R")
      (footprint "eagle-import:TP08R")
      (libsource (lib "eagle-import") (part "TPTP08R"))
    )
    (comp (ref "U1")
      (value "ST_MICRO_BAT_CHARGER_L6924U013")
      (footprint "eagle-import:BAT_CHARGE_ST_MICRO_L6924U")
      (fields (field (name "MFG") "ST Micro") (field (name "PARTNUM") "L6924UTR"))
      (libsource (lib "eagle-import") (part "ST_MICRO_BAT_CHARGER_L6924U013"))
    )
    (comp (ref "U2")
      (value "TPS63021")
      (footprint "eagle-import:QFN-14-POWERPAD3X4DSJ")
      (fields
        (field (name "MFG") "TI")
        (field (name "MPN") "TPS63021DSJ")
        (field (name "MPN_1") "TPS63021DSJR")
      )
      (libsource (lib "eagle-import") (part "TPS63021"))
    )
    (comp (ref "U3")
      (value "MICROCHIP_FLASH_MEM")
      (footprint "eagle-import:TDFN8_5X6")
      (fields (field (name "MFG") "MICROCHIP") (field (name "MPN") "SST26VF016BT-104I/MF"))
      (libsource (lib "eagle-import") (part "MICROCHIP_FLASH_MEM"))
    )
    (comp (ref "U4")
      (value "DIODE_DUAL_SCHOTKEY")
      (footprint "eagle-import:SOT23-3")
      (fields (field (name "MFG") "FAIRCHILD") (field (name "MPN") "BAT54C"))
      (libsource (lib "eagle-import") (part "DIODE_DUAL_SCHOTKEY"))
    )
    (comp (ref "U5")
      (value "MK20DX128VLH5")
      (footprint "eagle-import:MK20DX128VLH5")
      (fields (field (name "MFG") "Freescale") (field (name "MPN") "MK22FN1M0VLH12"))
      (libsource (lib "eagle-import") (part "MK20DX128VLH5"))
    )
    (comp (ref "U6")
      (value "FREESCALE_MKL17Z256VFM4")
      (footprint "eagle-import:QFN_32_5X5")
      (fields (field (name "MFG") "FREESCALE") (field (name "MPN") "MKL17Z256VFM4"))
      (libsource (lib "eagle-import") (part "FREESCALE_MKL17Z256VFM4"))
    )
    (comp (ref "U7")
      (value "PESD12VL2BT,215")
      (footprint "eagle-import:SOT23")
      (fields (field (name "MFG") "NXP"))
      (libsource (lib "eagle-import") (part "PESD12VL2BT,215"))
    )
    (comp (ref "U8")
      (value "VOLTAGE_TRANSLATOR_4_BIT")
      (footprint "eagle-import:UQFN_16")
      (fields (field (name "MFG") "TI") (field (name "MPN") "SN74AVC4T774RSVR"))
      (libsource (lib "eagle-import") (part "VOLTAGE_TRANSLATOR_4_BIT"))
    )
    (comp (ref "U9")
      (value "PESD12VL2BT,215")
      (footprint "eagle-import:SOT23")
      (fields (field (name "MFG") "NXP"))
      (libsource (lib "eagle-import") (part "PESD12VL2BT,215"))
    )
    (comp (ref "U10")
      (value "BOOST_5V_TI_TPS81256")
      (footprint "eagle-import:MICRO_SIP_3X3")
      (fields (field (name "MFG") "TI") (field (name "MPN") "TPS81256SIPT"))
      (libsource (lib "eagle-import") (part "BOOST_5V_TI_TPS81256"))
    )
    (comp (ref "U19")
      (value "MAX1704X")
      (footprint "eagle-import:TDFN-8")
      (description "Battery Fuel Gauge")
      (fields (field (name "MFG") "Maxim") (field (name "MPN") "MAX17043G+U"))
      (libsource (lib "eagle-import") (part "MAX1704X"))
    )
    (comp (ref "X1")
      (value "16 MHz")
      (footprint "eagle-import:CRYSTAL_RESONATOR_MURATA_CSTCE")
      (fields (field (name "MFG") "MURATA") (field (name "MPN") "CSTCE16M0V53-R0"))
      (libsource (lib "eagle-import") (part "CERAMIC_RESONATOR_16MHZ_MURATA_CSTCE"))
    )
    (comp (ref "X2")
      (value "32.768 kHz")
      (footprint "eagle-import:CRYSTAL_ST3215SB")
      (fields (field (name "MFG") "AVX/ELCO/KYOCERA") (field (name "MPN") "ST3215SB32768E0HPWBB"))
      (libsource (lib "eagle-import") (part "CRYSTAL_32.768K_AVX"))
    )
    (comp (ref "X3")
      (value "32.768 kHz")
      (footprint "eagle-import:CRYSTAL_ST3215SB")
      (fields (field (name "MFG") "AVX/ELCO/KYOCERA") (field (name "MPN") "ST3215SB32768E0HPWBB"))
      (libsource (lib "eagle-import") (part "CRYSTAL_32.768K_AVX"))
    )
  )
  (nets
    (net (code "1") (name "/+3.3V") (class "Default")
      (node (ref "C35") (pin "1") (pinfunction "1_1") (pintype "passive"))
      (node (ref "C36") (pin "1") (pinfunction "1_1") (pintype "passive"))
      (node (ref "C37") (pin "1") (pinfunction "1_1") (pintype "passive"))
      (node (ref "C38") (pin "1") (pinfunction "1_1") (pintype "passive"))
      (node (ref "D2") (pin "ANODE") (pinfunction "ANODE_ANODE") (pintype "bidirectional"))
      (node (ref "D6") (pin "ANODE") (pinfunction "ANODE_ANODE") (pintype "bidirectional"))
      (node (ref "J7") (pin "1") (pinfunction "P$1_1") (pintype "bidirectional"))
      (node (ref "J8") (pin "1") (pinfunction "P$1_1") (pintype "bidirectional"))
      (node (ref "J9") (pin "2") (pinfunction "2_2") (pintype "bidirectional"))
      (node (ref "JRIGHT_B") (pin "3") (pinfunction "3_3") (pintype "passive"))
      (node (ref "R12") (pin "1") (pinfunction "1_1") (pintype "passive"))
      (node (ref "R16") (pin "1") (pinfunction "1_1") (pintype "passive"))
      (node (ref "R17") (pin "1") (pinfunction "1_1") (pintype "passive"))
      (node (ref "R18") (pin "1") (pinfunction "1_1") (pintype "passive"))
      (node (ref "R2") (pin "2") (pinfunction "2_2") (pintype "passive"))
      (node (ref "R20") (pin "1") (pinfunction "1_1") (pintype "passive"))
      (node (ref "R21") (pin "1") (pinfunction "1_1") (pintype "passive"))
      (node (ref "R24") (pin "2") (pinfunction "2_2") (pintype "passive"))
      (node (ref "R27") (pin "1") (pinfunction "1_1") (pintype "passive"))
      (node (ref "R35") (pin "2") (pinfunction "2_2") (pintype "passive"))
      (node (ref "R4") (pin "1") (pinfunction "1_1") (pintype "passive"))
      (node (ref "R40") (pin "2") (pinfunction "2_2") (pintype "passive"))
      (node (ref "R42") (pin "2") (pinfunction "2_2") (pintype "passive"))
      (node (ref "R47") (pin "2") (pinfunction "2_2") (pintype "passive"))
      (node (ref "R48") (pin "1") (pinfunction "1_1") (pintype "passive"))
      (node (ref "R60") (pin "1") (pinfunction "1_1") (pintype "passive"))
      (node (ref "R67") (pin "2") (pinfunction "2_2") (pintype "passive"))
      (node (ref "TP9") (pin "TP") (pinfunction "TP_TP") (pintype "input"))
    )
    (net (code "2") (name "/+3.3V_GOOD") (class "Default")
      (node (ref "R42") (pin "1") (pinfunction "1_1") (pintype "passive"))
      (node (ref "U2") (pin "14") (pinfunction "PG_14") (pintype "bidirectional"))
      (node (ref "U5") (pin "39") (pinfunction "PTB16_39") (pintype "bidirectional"))
    )
    (net (code "3") (name "/+5V") (class "Default")
      (node (ref "D8") (pin "ANODE") (pinfunction "ANODE_ANODE") (pintype "bidirectional"))
      (node (ref "JRIGHT_B") (pin "4") (pinfunction "4_4") (pintype "passive"))
      (node (ref "R1") (pin "2") (pinfunction "2_2") (pintype "passive"))
      (node (ref "TP15") (pin "TP") (pinfunction "TP_TP") (pintype "input"))
    )
    (net (code "4") (name "/5V_EN") (class "Default")
      (node (ref "R11") (pin "1") (pinfunction "1_1") (pintype "passive"))
      (node (ref "R12") (pin "2") (pinfunction "2_2") (pintype "passive"))
      (node (ref "U5") (pin "40") (pinfunction "PTB17_40") (pintype "bidirectional"))
    )
    (net (code "5") (name "/AGND") (class "Default")
      (node (ref "C13") (pin "2") (pinfunction "2_2") (pintype "passive"))
      (node (ref "C14") (pin "2") (pinfunction "2_2") (pintype "passive"))
      (node (ref "C15") (pin "2") (pinfunction "2_2") (pintype "passive"))
      (node (ref "JRIGHT_B") (pin "1") (pinfunction "1_1") (pintype "passive"))
      (node (ref "L3") (pin "1") (pinfunction "P$1_1") (pintype "bidirectional"))
      (node (ref "U5") (pin "15") (pinfunction "VREFL_15") (pintype "bidirectional"))
      (node (ref "U5") (pin "16") (pinfunction "VSSA_16") (pintype "bidirectional"))
    )
    (net (code "6") (name "/ANT_DET$62") (class "Default")
      (node (ref "SARA1") (pin "62") (pinfunction "ANT_DET$62_62") (pintype "power_in"))
    )
    (net (code "7") (name "/AREF") (class "Default")
      (node (ref "C14") (pin "1") (pinfunction "1_1") (pintype "passive"))
      (node (ref "R19") (pin "2") (pinfunction "2_2") (pintype "passive"))
      (node (ref "U5") (pin "14") (pinfunction "VREFH_14") (pintype "bidirectional"))
    )
    (net (code "8") (name "/BATMON_ALT") (class "Default")
      (node (ref "U19") (pin "5") (pinfunction "ALT_5") (pintype "bidirectional"))
      (node (ref "U6") (pin "12") (pinfunction "PTA2_12") (pintype "bidirectional"))
    )
    (net (code "9") (name "/BAT_CHG_ST1") (class "Default")
      (node (ref "U1") (pin "4") (pinfunction "ST1_4") (pintype "bidirectional"))
      (node (ref "U5") (pin "10") (pinfunction "PGA0_DM_10") (pintype "bidirectional"))
    )
    (net (code "10") (name "/BAT_CHG_ST2") (class "Default")
      (node (ref "U1") (pin "3") (pinfunction "ST2_3") (pintype "bidirectional"))
      (node (ref "U5") (pin "11") (pinfunction "PGA1_DP_11") (pintype "bidirectional"))
    )
    (net (code "11") (name "/BL_SCL") (class "Default")
      (node (ref "R40") (pin "1") (pinfunction "1_1") (pintype "passive"))
      (node (ref "R58") (pin "2") (pinfunction "2_2") (pintype "passive"))
      (node (ref "U19") (pin "7") (pinfunction "SCL_7") (pintype "bidirectional"))
      (node (ref "U5") (pin "37") (pinfunction "PTB2_37") (pintype "bidirectional"))
    )
    (net (code "12") (name "/BL_SDA") (class "Default")
      (node (ref "R35") (pin "1") (pinfunction "1_1") (pintype "passive"))
      (node (ref "R59") (pin "2") (pinfunction "2_2") (pintype "passive"))
      (node (ref "U19") (pin "8") (pinfunction "SDA_8") (pintype "bidirectional"))
      (node (ref "U5") (pin "38") (pinfunction "PTB3_38") (pintype "bidirectional"))
    )
    (net (code "13") (name "/EZP_CS") (class "Default")
      (node (ref "R55") (pin "2") (pinfunction "2_2") (pintype "passive"))
      (node (ref "U5") (pin "26") (pinfunction "PTA4_26") (pintype "bidirectional"))
    )
    (net (code "14") (name "/GPIO4$25") (class "Default")
      (node (ref "SARA1") (pin "25") (pinfunction "GPIO4$25_25") (pintype "power_in"))
    )
    (net (code "15") (name "/I2S_TXD$35") (class "Default")
      (node (ref "SARA1") (pin "35") (pinfunction "I2S_TXD$35_35") (pintype "power_in"))
    )
    (net (code "16") (name "/I2S_WA$34") (class "Default")
      (node (ref "SARA1") (pin "34") (pinfunction "I2S_WA$34_34") (pintype "power_in"))
    )
    (net (code "17") (name "/LISA_MISO") (class "Default")
      (node (ref "LISA1") (pin "SPI_MISO/GPIO12") (pinfunction "SPI_MISO/GPIO12_SPI_MISO/GPIO12") (pintype "bidirectional"))
    )
    (net (code "18") (name "/LISA_MOSI") (class "Default")
      (node (ref "LISA1") (pin "SPI_MOSI/GPIO11") (pinfunction "SPI_MOSI/GPIO11_SPI_MOSI/GPIO11") (pintype "bidirectional"))
    )
    (net (code "19") (name "/LISA_SCLK") (class "Default")
      (node (ref "LISA1") (pin "SPI_SCLK/GPIO10") (pinfunction "SPI_SCLK/GPIO10_SPI_SCLK/GPIO10") (pintype "bidirectional"))
    )
    (net (code "20") (name "/LISA_SRDY") (class "Default")
      (node (ref "LISA1") (pin "SPI_SRDY/GPIO13") (pinfunction "SPI_SRDY/GPIO13_SPI_SRDY/GPIO13") (pintype "bidirectional"))
    )
    (net (code "21") (name "/M1_CTRL_M2_RESET") (class "Default")
      (node (ref "R23") (pin "2") (pinfunction "2_2") (pintype "passive"))
      (node (ref "U5") (pin "41") (pinfunction "PTB18_41") (pintype "bidirectional"))
    )
    (net (code "22") (name "/M1_RESET") (class "Default")
      (node (ref "C24") (pin "1") (pinfunction "1_1") (pintype "passive"))
      (node (ref "C51") (pin "1") (pinfunction "1_1") (pintype "passive"))
      (node (ref "J8") (pin "10") (pinfunction "P$10_10") (pintype "bidirectional"))
      (node (ref "JRIGHT_B") (pin "2") (pinfunction "2_2") (pintype "passive"))
      (node (ref "L6") (pin "2") (pinfunction "P$2_2") (pintype "bidirectional"))
      (node (ref "R22") (pin "2") (pinfunction "2_2") (pintype "passive"))
      (node (ref "R47") (pin "1") (pinfunction "1_1") (pintype "passive"))
      (node (ref "SW_USR_RST") (pin "A") (pinfunction "P$1_A") (pintype "bidirectional"))
      (node (ref "SW_USR_RST") (pin "A2") (pinfunction "P$1_A2") (pintype "bidirectional"))
      (node (ref "TP17") (pin "TP") (pinfunction "TP_TP") (pintype "input"))
      (node (ref "U5") (pin "34") (pinfunction "RESET_B_34") (pintype "bidirectional"))
    )
    (net (code "23") (name "/M1_TCK_SWDCLK") (class "Default")
      (node (ref "J8") (pin "4") (pinfunction "P$4_4") (pintype "bidirectional"))
      (node (ref "R54") (pin "2") (pinfunction "2_2") (pintype "passive"))
      (node (ref "TP4") (pin "TP") (pinfunction "TP_TP") (pintype "input"))
      (node (ref "U5") (pin "22") (pinfunction "PTA0_22") (pintype "bidirectional"))
    )
    (net (code "24") (name "/M1_TDI") (class "Default")
      (node (ref "J8") (pin "8") (pinfunction "P$8_8") (pintype "bidirectional"))
      (node (ref "R57") (pin "2") (pinfunction "2_2") (pintype "passive"))
      (node (ref "R66") (pin "2") (pinfunction "2_2") (pintype "passive"))
      (node (ref "TP6") (pin "TP") (pinfunction "TP_TP") (pintype "input"))
      (node (ref "U5") (pin "23") (pinfunction "PTA1_23") (pintype "bidirectional"))
    )
    (net (code "25") (name "/M1_TDO_SWO") (class "Default")
      (node (ref "J8") (pin "6") (pinfunction "P$6_6") (pintype "bidirectional"))
      (node (ref "R56") (pin "2") (pinfunction "2_2") (pintype "passive"))
      (node (ref "TP7") (pin "TP") (pinfunction "TP_TP") (pintype "input"))
      (node (ref "U5") (pin "24") (pinfunction "PTA2_24") (pintype "bidirectional"))
    )
    (net (code "26") (name "/M1_TMS_SWDIO") (class "Default")
      (node (ref "J8") (pin "2") (pinfunction "P$2_2") (pintype "bidirectional"))
      (node (ref "R14") (pin "2") (pinfunction "2_2") (pintype "passive"))
      (node (ref "TP8") (pin "TP") (pinfunction "TP_TP") (pintype "input"))
      (node (ref "U5") (pin "25") (pinfunction "PTA3_25") (pintype "bidirectional"))
    )
    (net (code "27") (name "/M1_TX_TO_M2_RX") (class "Default")
      (node (ref "R61") (pin "1") (pinfunction "1_1") (pintype "passive"))
      (node (ref "U5") (pin "49") (pinfunction "PTC4_49") (pintype "bidirectional"))
    )
    (net (code "28") (name "/M2_MISO") (class "Default")
      (node (ref "U3") (pin "2") (pinfunction "SO_2") (pintype "bidirectional"))
      (node (ref "U6") (pin "1") (pinfunction "PTE0_1") (pintype "bidirectional"))
    )
    (net (code "29") (name "/M2_MOSI") (class "Default")
      (node (ref "U3") (pin "5") (pinfunction "SI_5") (pintype "bidirectional"))
      (node (ref "U6") (pin "2") (pinfunction "PTE1_2") (pintype "bidirectional"))
    )
    (net (code "30") (name "/M2_RESET") (class "Default")
      (node (ref "J7") (pin "10") (pinfunction "P$10_10") (pintype "bidirectional"))
      (node (ref "R23") (pin "1") (pinfunction "1_1") (pintype "passive"))
      (node (ref "SW_SYS_RST") (pin "A") (pinfunction "P$1_A") (pintype "bidirectional"))
      (node (ref "SW_SYS_RST") (pin "A2") (pinfunction "P$1_A2") (pintype "bidirectional"))
      (node (ref "TP27") (pin "TP") (pinfunction "TP_TP") (pintype "input"))
      (node (ref "U6") (pin "19") (pinfunction "RESET_B_PTA20_19") (pintype "bidirectional"))
    )
    (net (code "31") (name "/M2_SCK") (class "Default")
      (node (ref "U3") (pin "6") (pinfunction "SCK_6") (pintype "bidirectional"))
      (node (ref "U6") (pin "30") (pinfunction "PTD5_30") (pintype "bidirectional"))
    )
    (net (code "32") (name "/M2_SS") (class "Default")
      (node (ref "U3") (pin "1") (pinfunction "~{CE}_1") (pintype "bidirectional"))
      (node (ref "U6") (pin "29") (pinfunction "PTD4_29") (pintype "bidirectional"))
    )
    (net (code "33") (name "/M2_TCK_SWDCLK") (class "Default")
      (node (ref "J7") (pin "4") (pinfunction "P$4_4") (pintype "bidirectional"))
      (node (ref "TP14") (pin "TP") (pinfunction "TP_TP") (pintype "input"))
      (node (ref "U6") (pin "10") (pinfunction "PTA0_10") (pintype "bidirectional"))
    )
    (net (code "34") (name "/M2_TDI") (class "Default")
      (node (ref "J7") (pin "8") (pinfunction "P$8_8") (pintype "bidirectional"))
      (node (ref "TP26") (pin "TP") (pinfunction "TP_TP") (pintype "input"))
    )
    (net (code "35") (name "/M2_TDO_SWO") (class "Default")
      (node (ref "J7") (pin "6") (pinfunction "P$6_6") (pintype "bidirectional"))
      (node (ref "TP25") (pin "TP") (pinfunction "TP_TP") (pintype "input"))
    )
    (net (code "36") (name "/M2_TMS_SWDIO") (class "Default")
      (node (ref "J7") (pin "2") (pinfunction "P$2_2") (pintype "bidirectional"))
      (node (ref "TP2") (pin "TP") (pinfunction "TP_TP") (pintype "input"))
      (node (ref "U6") (pin "13") (pinfunction "PTA3_13") (pintype "bidirectional"))
    )
    (net (code "37") (name "/M2_TX_TO_M1_RX") (class "Default")
      (node (ref "R62") (pin "1") (pinfunction "1_1") (pintype "passive"))
      (node (ref "U5") (pin "46") (pinfunction "PTC3_46") (pintype "bidirectional"))
    )
    (net (code "38") (name "/M2_UBLOX_RX") (class "Default")
      (node (ref "R63") (pin "1") (pinfunction "1_1") (pintype "passive"))
      (node (ref "TP24") (pin "TP") (pinfunction "TP_TP") (pintype "input"))
      (node (ref "U8") (pin "P$2") (pinfunction "A2_P$2") (pintype "bidirectional"))
    )
    (net (code "39") (name "/M2_UBLOX_TX") (class "Default")
      (node (ref "R64") (pin "1") (pinfunction "1_1") (pintype "passive"))
      (node (ref "TP23") (pin "TP") (pinfunction "TP_TP") (pintype "input"))
      (node (ref "U8") (pin "P$1") (pinfunction "A1_P$1") (pintype "bidirectional"))
    )
    (net (code "40") (name "/RSVD$31") (class "Default")
      (node (ref "SARA1") (pin "31") (pinfunction "RSVD$31_31") (pintype "power_in"))
    )
    (net (code "41") (name "/SCL$27") (class "Default")
      (node (ref "SARA1") (pin "27") (pinfunction "SCL$27_27") (pintype "power_in"))
    )
    (net (code "42") (name "/SDA$26") (class "Default")
      (node (ref "SARA1") (pin "26") (pinfunction "SDA$26_26") (pintype "power_in"))
    )
    (net (code "43") (name "/UBLOX_1.8V_SUPPLY") (class "Default")
      (node (ref "LISA1") (pin "V_INT") (pinfunction "V_INT_V_INT") (pintype "bidirectional"))
      (node (ref "R49") (pin "1") (pinfunction "1_1") (pintype "passive"))
      (node (ref "SARA1") (pin "4") (pinfunction "V_INT$4_4") (pintype "bidirectional"))
    )
    (net (code "44") (name "/UBLOX_ANT") (class "Default")
      (node (ref "L4") (pin "1") (pinfunction "P$1_1") (pintype "bidirectional"))
      (node (ref "LISA1") (pin "ANT") (pinfunction "ANT_ANT") (pintype "bidirectional"))
      (node (ref "R29") (pin "2") (pinfunction "2_2") (pintype "passive"))
      (node (ref "SARA1") (pin "56") (pinfunction "ANT$56_56") (pintype "power_in"))
    )
    (net (code "45") (name "/UBLOX_ANT_FINAL") (class "Default")
      (node (ref "ANT_UFL") (pin "SIGNAL") (pinfunction "SIGNAL_SIGNAL") (pintype "bidirectional"))
      (node (ref "C77") (pin "1") (pinfunction "1_1") (pintype "passive"))
      (node (ref "L9") (pin "1") (pinfunction "P$1_1") (pintype "bidirectional"))
      (node (ref "R29") (pin "1") (pinfunction "1_1") (pintype "passive"))
    )
    (net (code "46") (name "/UBLOX_ANT_IND") (class "Default")
      (node (ref "LISA1") (pin "GPIO1") (pinfunction "GPIO1_GPIO1") (pintype "bidirectional"))
      (node (ref "R52") (pin "1") (pinfunction "1_1") (pintype "passive"))
      (node (ref "SARA1") (pin "16") (pinfunction "GPIO1$16_16") (pintype "bidirectional"))
    )
    (net (code "47") (name "/UBLOX_GPIO3") (class "Default")
      (node (ref "LISA1") (pin "GPIO3") (pinfunction "GPIO3_GPIO3") (pintype "bidirectional"))
    )
    (net (code "48") (name "/UBLOX_GPIO4") (class "Default")
      (node (ref "LISA1") (pin "GPIO4") (pinfunction "GPIO4_GPIO4") (pintype "bidirectional"))
    )
    (net (code "49") (name "/UBLOX_PWR_IN") (class "Default")
      (node (ref "F1") (pin "2") (pinfunction "P$2_2") (pintype "bidirectional"))
      (node (ref "J9") (pin "1") (pinfunction "1_1") (pintype "bidirectional"))
      (node (ref "J9") (pin "3") (pinfunction "3_3") (pintype "bidirectional"))
      (node (ref "R27") (pin "2") (pinfunction "2_2") (pintype "passive"))
      (node (ref "R34") (pin "2") (pinfunction "2_2") (pintype "passive"))
    )
    (net (code "50") (name "/UBLOX_PWR_ON") (class "Default")
      (node (ref "LISA1") (pin "PWR_ON") (pinfunction "PWR_ON_PWR_ON") (pintype "bidirectional"))
      (node (ref "R51") (pin "1") (pinfunction "1_1") (pintype "passive"))
      (node (ref "SARA1") (pin "15") (pinfunction "PWR_ON$15_15") (pintype "bidirectional"))
      (node (ref "TP3") (pin "TP") (pinfunction "PP_TP") (pintype "input"))
      (node (ref "U6") (pin "11") (pinfunction "PTA1_11") (pintype "bidirectional"))
    )
    (net (code "51") (name "/UBLOX_RESET_N") (class "Default")
      (node (ref "C43") (pin "1") (pinfunction "1_1") (pintype "passive"))
      (node (ref "L6") (pin "1") (pinfunction "P$1_1") (pintype "bidirectional"))
      (node (ref "LISA1") (pin "RESET_N") (pinfunction "RESET_N_RESET_N") (pintype "bidirectional"))
      (node (ref "SARA1") (pin "18") (pinfunction "RESET_N$18_18") (pintype "bidirectional"))
    )
    (net (code "52") (name "/UBLOX_RXD") (class "Default")
      (node (ref "LISA1") (pin "RXD") (pinfunction "RXD(OUTPUT)_RXD") (pintype "bidirectional"))
      (node (ref "SARA1") (pin "13") (pinfunction "RXD$13_13") (pintype "bidirectional"))
      (node (ref "TP22") (pin "TP") (pinfunction "TP_TP") (pintype "input"))
      (node (ref "U8") (pin "P$11") (pinfunction "B2_P$11") (pintype "bidirectional"))
    )
    (net (code "53") (name "/UBLOX_SARA_USB_D_N") (class "Default")
      (node (ref "R37") (pin "2") (pinfunction "2_2") (pintype "passive"))
      (node (ref "SARA1") (pin "28") (pinfunction "USB_D-$28_28") (pintype "power_in"))
    )
    (net (code "54") (name "/UBLOX_SARA_USB_D_P") (class "Default")
      (node (ref "R36") (pin "2") (pinfunction "2_2") (pintype "passive"))
      (node (ref "SARA1") (pin "29") (pinfunction "USB_D+$29_29") (pintype "power_in"))
    )
    (net (code "55") (name "/UBLOX_SCL") (class "Default")
      (node (ref "LISA1") (pin "SCL") (pinfunction "SCL_SCL") (pintype "bidirectional"))
    )
    (net (code "56") (name "/UBLOX_SDA") (class "Default")
      (node (ref "LISA1") (pin "SDA") (pinfunction "SDA_SDA") (pintype "bidirectional"))
    )
    (net (code "57") (name "/UBLOX_SIM_CLK") (class "Default")
      (node (ref "C42") (pin "1") (pinfunction "1_1") (pintype "passive"))
      (node (ref "LISA1") (pin "SIM_CLK") (pinfunction "SIM_CLK_SIM_CLK") (pintype "bidirectional"))
      (node (ref "SARA1") (pin "38") (pinfunction "SIM_CLK$38_38") (pintype "power_in"))
      (node (ref "SIM1") (pin "C3-CLK") (pinfunction "CLK_C3-CLK") (pintype "bidirectional"))
    )
    (net (code "58") (name "/UBLOX_SIM_IO") (class "Default")
      (node (ref "C44") (pin "1") (pinfunction "1_1") (pintype "passive"))
      (node (ref "LISA1") (pin "SIM_IO") (pinfunction "SIM_IO_SIM_IO") (pintype "bidirectional"))
      (node (ref "SARA1") (pin "39") (pinfunction "SIM_IO$39_39") (pintype "power_in"))
      (node (ref "SIM1") (pin "C7-IO") (pinfunction "IO_C7-IO") (pintype "bidirectional"))
    )
    (net (code "59") (name "/UBLOX_SIM_RST") (class "Default")
      (node (ref "C41") (pin "1") (pinfunction "1_1") (pintype "passive"))
      (node (ref "LISA1") (pin "SIM_RST") (pinfunction "SIM_RST_SIM_RST") (pintype "bidirectional"))
      (node (ref "SARA1") (pin "40") (pinfunction "SIM_RST$40_40") (pintype "power_in"))
      (node (ref "SIM1") (pin "C2-RST") (pinfunction "RST_C2-RST") (pintype "bidirectional"))
    )
    (net (code "60") (name "/UBLOX_SIM_VSIM") (class "Default")
      (node (ref "C2") (pin "1") (pinfunction "1_1") (pintype "passive"))
      (node (ref "C45") (pin "1") (pinfunction "1_1") (pintype "passive"))
      (node (ref "LISA1") (pin "VSIM") (pinfunction "VSIM_VSIM") (pintype "power_in"))
      (node (ref "SARA1") (pin "41") (pinfunction "VSIM$41_41") (pintype "bidirectional"))
      (node (ref "SIM1") (pin "C1-VCC") (pinfunction "VCC_C1-VCC") (pintype "bidirectional"))
      (node (ref "SIM1") (pin "C6-VPP") (pinfunction "VCC2_C6-VPP") (pintype "bidirectional"))
    )
    (net (code "61") (name "/UBLOX_TXD") (class "Default")
      (node (ref "LISA1") (pin "TXD") (pinfunction "TXD(INPUT)_TXD") (pintype "bidirectional"))
      (node (ref "SARA1") (pin "12") (pinfunction "TXD$12_12") (pintype "power_in"))
      (node (ref "TP21") (pin "TP") (pinfunction "TP_TP") (pintype "input"))
      (node (ref "U8") (pin "P$12") (pinfunction "B1_P$12") (pintype "bidirectional"))
    )
    (net (code "62") (name "/UBLOX_USB_DET") (class "Default")
      (node (ref "LISA1") (pin "VUSB_DET") (pinfunction "VUSB_DET_VUSB_DET") (pintype "bidirectional"))
      (node (ref "R32") (pin "1") (pinfunction "1_1") (pintype "passive"))
      (node (ref "SARA1") (pin "17") (pinfunction "V_USB_DET$17_17") (pintype "bidirectional"))
    )
    (net (code "63") (name "/UBLOX_USB_D_N") (class "Default")
      (node (ref "LISA1") (pin "USB_D-") (pinfunction "USB_D-_USB_D-") (pintype "bidirectional"))
      (node (ref "R31") (pin "1") (pinfunction "1_1") (pintype "passive"))
    )
    (net (code "64") (name "/UBLOX_USB_D_P") (class "Default")
      (node (ref "LISA1") (pin "USB_D+") (pinfunction "USB_D+_USB_D+") (pintype "bidirectional"))
      (node (ref "R30") (pin "1") (pinfunction "1_1") (pintype "passive"))
    )
    (net (code "65") (name "/UBLOX_VCC") (class "Default")
      (node (ref "L7") (pin "2") (pinfunction "P$2_2") (pintype "bidirectional"))
      (node (ref "LISA1") (pin "VCC$61") (pinfunction "VCC$61_VCC$61") (pintype "power_in"))
      (node (ref "LISA1") (pin "VCC$62") (pinfunction "VCC$62_VCC$62") (pintype "power_in"))
      (node (ref "LISA1") (pin "VCC$63") (pinfunction "VCC$63_VCC$63") (pintype "power_in"))
      (node (ref "SARA1") (pin "51") (pinfunction "VCC$51_51") (pintype "bidirectional"))
      (node (ref "SARA1") (pin "52") (pinfunction "VCC$52_52") (pintype "bidirectional"))
      (node (ref "SARA1") (pin "53") (pinfunction "VCC$53_53") (pintype "bidirectional"))
      (node (ref "TP30") (pin "TP") (pinfunction "TP_TP") (pintype "input"))
    )
    (net (code "66") (name "/UBLOX_VCC_PRE") (class "Default")
      (node (ref "C57") (pin "P$1") (pinfunction "POS_P$1") (pintype "bidirectional"))
      (node (ref "C58") (pin "1") (pinfunction "1_1") (pintype "passive"))
      (node (ref "C59") (pin "1") (pinfunction "1_1") (pintype "passive"))
      (node (ref "C60") (pin "1") (pinfunction "1_1") (pintype "passive"))
      (node (ref "C61") (pin "1") (pinfunction "1_1") (pintype "passive"))
      (node (ref "D3") (pin "ANODE") (pinfunction "ANODE_ANODE") (pintype "bidirectional"))
      (node (ref "F1") (pin "1") (pinfunction "P$1_1") (pintype "bidirectional"))
      (node (ref "L7") (pin "1") (pinfunction "P$1_1") (pintype "bidirectional"))
      (node (ref "TP28") (pin "TP") (pinfunction "TP_TP") (pintype "input"))
    )
    (net (code "67") (name "/UBLOX_V_BCKP") (class "Default")
      (node (ref "LISA1") (pin "V_BCKP") (pinfunction "V_BCKP_V_BCKP") (pintype "power_in"))
      (node (ref "R51") (pin "2") (pinfunction "2_2") (pintype "passive"))
      (node (ref "SARA1") (pin "2") (pinfunction "V_BCKP$2_2") (pintype "bidirectional"))
    )
    (net (code "68") (name "/UBLOX_WAKE_M2") (class "Default")
      (node (ref "LISA1") (pin "GPIO2") (pinfunction "GPIO2_GPIO2") (pintype "bidirectional"))
      (node (ref "SARA1") (pin "23") (pinfunction "GPIO2$23_23") (pintype "power_in"))
      (node (ref "U6") (pin "23") (pinfunction "PTC2_23") (pintype "bidirectional"))
    )
    (net (code "69") (name "/USB_5V") (class "Default")
      (node (ref "F6") (pin "1") (pinfunction "P$1_1") (pintype "bidirectional"))
      (node (ref "J1") (pin "VCC") (pinfunction "VBUS_VCC") (pintype "bidirectional"))
      (node (ref "JLEFT_A") (pin "6") (pinfunction "6_6") (pintype "passive"))
      (node (ref "TP1") (pin "TP") (pinfunction "TP_TP") (pintype "input"))
      (node (ref "U7") (pin "1") (pinfunction "P$1_1") (pintype "bidirectional"))
    )
    (net (code "70") (name "/USB_D_N") (class "Default")
      (node (ref "RN1") (pin "7") (pinfunction "2_7") (pintype "passive"))
      (node (ref "U5") (pin "6") (pinfunction "USB0_DM_6") (pintype "bidirectional"))
      (node (ref "U9") (pin "1") (pinfunction "P$1_1") (pintype "bidirectional"))
    )
    (net (code "71") (name "/USB_D_P") (class "Default")
      (node (ref "RN1") (pin "6") (pinfunction "2_6") (pintype "passive"))
      (node (ref "U5") (pin "5") (pinfunction "USB0_DP_5") (pintype "bidirectional"))
      (node (ref "U9") (pin "2") (pinfunction "P$2_2") (pintype "bidirectional"))
    )
    (net (code "72") (name "/USB_ID") (class "Default")
      (node (ref "J1") (pin "ID") (pinfunction "ID_ID") (pintype "bidirectional"))
      (node (ref "R66") (pin "1") (pinfunction "1_1") (pintype "passive"))
      (node (ref "U7") (pin "2") (pinfunction "P$2_2") (pintype "bidirectional"))
    )
    (net (code "73") (name "/USB_IN") (class "Default")
      (node (ref "C1") (pin "1") (pinfunction "1_1") (pintype "passive"))
      (node (ref "C11") (pin "1") (pinfunction "1_1") (pintype "passive"))
      (node (ref "C12") (pin "1") (pinfunction "1_1") (pintype "passive"))
      (node (ref "F6") (pin "2") (pinfunction "P$2_2") (pintype "bidirectional"))
      (node (ref "J2") (pin "2") (pinfunction "2_2") (pintype "bidirectional"))
      (node (ref "J2") (pin "4") (pinfunction "4_4") (pintype "bidirectional"))
      (node (ref "R6") (pin "1") (pinfunction "1_1") (pintype "passive"))
      (node (ref "R72") (pin "1") (pinfunction "1_1") (pintype "passive"))
      (node (ref "TP5") (pin "TP") (pinfunction "TP_TP") (pintype "input"))
    )
    (net (code "74") (name "/USB_IN_D_N") (class "Default")
      (node (ref "J1") (pin "D-") (pinfunction "D-_D-") (pintype "bidirectional"))
      (node (ref "RN1") (pin "2") (pinfunction "1_2") (pintype "passive"))
    )
    (net (code "75") (name "/USB_IN_D_P") (class "Default")
      (node (ref "J1") (pin "D+") (pinfunction "D+_D+") (pintype "bidirectional"))
      (node (ref "RN1") (pin "3") (pinfunction "1_3") (pintype "passive"))
    )
    (net (code "76") (name "/USER01") (class "Default")
      (node (ref "JLEFT_B") (pin "3") (pinfunction "3_3") (pintype "passive"))
      (node (ref "U5") (pin "29") (pinfunction "PTA13_29") (pintype "bidirectional"))
    )
    (net (code "77") (name "/USER02") (class "Default")
      (node (ref "JLEFT_B") (pin "4") (pinfunction "4_4") (pintype "passive"))
      (node (ref "U5") (pin "28") (pinfunction "PTA12_28") (pintype "bidirectional"))
    )
    (net (code "78") (name "/USER03") (class "Default")
      (node (ref "JLEFT_B") (pin "5") (pinfunction "5_5") (pintype "passive"))
      (node (ref "U5") (pin "27") (pinfunction "PTA5_27") (pintype "bidirectional"))
    )
    (net (code "79") (name "/USER04") (class "Default")
      (node (ref "JLEFT_A") (pin "4") (pinfunction "4_4") (pintype "passive"))
      (node (ref "U5") (pin "1") (pinfunction "PTE0_1") (pintype "bidirectional"))
    )
    (net (code "80") (name "/USER05") (class "Default")
      (node (ref "JLEFT_A") (pin "3") (pinfunction "3_3") (pintype "passive"))
      (node (ref "U5") (pin "2") (pinfunction "PTE1_2") (pintype "bidirectional"))
    )
    (net (code "81") (name "/USER06") (class "Default")
      (node (ref "JLEFT_B") (pin "2") (pinfunction "2_2") (pintype "passive"))
      (node (ref "U5") (pin "35") (pinfunction "PTB0_35") (pintype "bidirectional"))
    )
    (net (code "82") (name "/USER07") (class "Default")
      (node (ref "JLEFT_B") (pin "6") (pinfunction "6_6") (pintype "passive"))
      (node (ref "U5") (pin "36") (pinfunction "PTB1_36") (pintype "bidirectional"))
    )
    (net (code "83") (name "/USER08") (class "Default")
      (node (ref "JLEFT_B") (pin "1") (pinfunction "1_1") (pintype "passive"))
      (node (ref "U5") (pin "18") (pinfunction "DAC0_OUT_18") (pintype "bidirectional"))
    )
    (net (code "84") (name "/USER09") (class "Default")
      (node (ref "JRIGHT_B") (pin "7") (pinfunction "7_7") (pintype "passive"))
      (node (ref "U5") (pin "45") (pinfunction "PTC2_45") (pintype "bidirectional"))
    )
    (net (code "85") (name "/USER10") (class "Default")
      (node (ref "JRIGHT_B") (pin "8") (pinfunction "8_8") (pintype "passive"))
      (node (ref "U5") (pin "44") (pinfunction "PTC1_44") (pintype "bidirectional"))
    )
    (net (code "86") (name "/USER11") (class "Default")
      (node (ref "JRIGHT_B") (pin "6") (pinfunction "6_6") (pintype "passive"))
      (node (ref "U5") (pin "43") (pinfunction "PTC0_43") (pintype "bidirectional"))
    )
    (net (code "87") (name "/USER12") (class "Default")
      (node (ref "JRIGHT_A") (pin "1") (pinfunction "1_1") (pintype "passive"))
      (node (ref "U5") (pin "53") (pinfunction "PTC8_53") (pintype "bidirectional"))
    )
    (net (code "88") (name "/USER13") (class "Default")
      (node (ref "JLEFT_A") (pin "2") (pinfunction "2_2") (pintype "passive"))
      (node (ref "U5") (pin "58") (pinfunction "PTD1_58") (pintype "bidirectional"))
    )
    (net (code "89") (name "/USER14") (class "Default")
      (node (ref "JLEFT_A") (pin "1") (pinfunction "1_1") (pintype "passive"))
      (node (ref "U5") (pin "59") (pinfunction "PTD2_59") (pintype "bidirectional"))
    )
    (net (code "90") (name "/USER15") (class "Default")
      (node (ref "JLEFT_B") (pin "7") (pinfunction "7_7") (pintype "passive"))
      (node (ref "U5") (pin "60") (pinfunction "PTD3_60") (pintype "bidirectional"))
    )
    (net (code "91") (name "/USER16") (class "Default")
      (node (ref "JRIGHT_A") (pin "3") (pinfunction "3_3") (pintype "passive"))
      (node (ref "U5") (pin "61") (pinfunction "PTD4_61") (pintype "bidirectional"))
    )
    (net (code "92") (name "/USER17") (class "Default")
      (node (ref "JLEFT_B") (pin "8") (pinfunction "8_8") (pintype "passive"))
      (node (ref "U5") (pin "62") (pinfunction "PTD5_62") (pintype "bidirectional"))
    )
    (net (code "93") (name "/USER18") (class "Default")
      (node (ref "JRIGHT_A") (pin "2") (pinfunction "2_2") (pintype "passive"))
      (node (ref "U5") (pin "63") (pinfunction "PTD6_63") (pintype "bidirectional"))
    )
    (net (code "94") (name "/USER19") (class "Default")
      (node (ref "JRIGHT_A") (pin "4") (pinfunction "4_4") (pintype "passive"))
      (node (ref "U5") (pin "64") (pinfunction "PTD7_64") (pintype "bidirectional"))
    )
    (net (code "95") (name "/USER22") (class "Default")
      (node (ref "JRIGHT_B") (pin "5") (pinfunction "5_5") (pintype "passive"))
      (node (ref "R74") (pin "2") (pinfunction "2_2") (pintype "passive"))
    )
    (net (code "96") (name "/USER25") (class "Default")
      (node (ref "R73") (pin "2") (pinfunction "2_2") (pintype "passive"))
    )
    (net (code "97") (name "/VBATT") (class "Default")
      (node (ref "D5") (pin "ANODE") (pinfunction "ANODE_ANODE") (pintype "bidirectional"))
      (node (ref "F3") (pin "1") (pinfunction "P$1_1") (pintype "bidirectional"))
      (node (ref "J2") (pin "1") (pinfunction "1_1") (pintype "bidirectional"))
      (node (ref "J20") (pin "BAT") (pinfunction "BAT_BAT") (pintype "bidirectional"))
      (node (ref "J9") (pin "4") (pinfunction "4_4") (pintype "bidirectional"))
      (node (ref "JRIGHT_A") (pin "6") (pinfunction "6_6") (pintype "passive"))
      (node (ref "L2") (pin "1") (pinfunction "P$1_1") (pintype "bidirectional"))
      (node (ref "R13") (pin "1") (pinfunction "1_1") (pintype "passive"))
      (node (ref "R34") (pin "1") (pinfunction "1_1") (pintype "passive"))
      (node (ref "R71") (pin "1") (pinfunction "1_1") (pintype "passive"))
      (node (ref "R72") (pin "2") (pinfunction "2_2") (pintype "passive"))
      (node (ref "TP13") (pin "TP") (pinfunction "TP_TP") (pintype "input"))
    )
    (net (code "98") (name "/VBATT_+3.3V") (class "Default")
      (node (ref "C33") (pin "1") (pinfunction "1_1") (pintype "passive"))
      (node (ref "C34") (pin "1") (pinfunction "1_1") (pintype "passive"))
      (node (ref "R71") (pin "2") (pinfunction "2_2") (pintype "passive"))
      (node (ref "U2") (pin "10") (pinfunction "VIN_10") (pintype "bidirectional"))
      (node (ref "U2") (pin "11") (pinfunction "VIN_11") (pintype "bidirectional"))
    )
    (net (code "99") (name "/VBATT_+5.0V") (class "Default")
      (node (ref "R13") (pin "2") (pinfunction "2_2") (pintype "passive"))
      (node (ref "U10") (pin "C1") (pinfunction "VIN_C1") (pintype "bidirectional"))
      (node (ref "U10") (pin "C2") (pinfunction "VIN_C2") (pintype "bidirectional"))
    )
    (net (code "100") (name "/VBATT_OUT") (class "Default")
      (node (ref "C21") (pin "1") (pinfunction "1_1") (pintype "passive"))
      (node (ref "F3") (pin "2") (pinfunction "P$2_2") (pintype "bidirectional"))
      (node (ref "R45") (pin "2") (pinfunction "2_2") (pintype "passive"))
      (node (ref "U1") (pin "10") (pinfunction "VOSNS_10") (pintype "bidirectional"))
      (node (ref "U1") (pin "11") (pinfunction "VOUT_11") (pintype "bidirectional"))
    )
    (net (code "101") (name "/WAKE_M1") (class "Default")
      (node (ref "D7") (pin "ANODE") (pinfunction "ANODE_ANODE") (pintype "bidirectional"))
      (node (ref "R74") (pin "1") (pinfunction "1_1") (pintype "passive"))
      (node (ref "U5") (pin "50") (pinfunction "PTC5_50") (pintype "bidirectional"))
      (node (ref "U6") (pin "28") (pinfunction "PTC7_28") (pintype "bidirectional"))
    )
    (net (code "102") (name "/WAKE_M2") (class "Default")
      (node (ref "R24") (pin "1") (pinfunction "1_1") (pintype "passive"))
      (node (ref "R73") (pin "1") (pinfunction "1_1") (pintype "passive"))
      (node (ref "SW_PGM") (pin "A") (pinfunction "P$1_A") (pintype "bidirectional"))
      (node (ref "SW_PGM") (pin "A2") (pinfunction "P$1_A2") (pintype "bidirectional"))
      (node (ref "U5") (pin "54") (pinfunction "PTC9_54") (pintype "bidirectional"))
      (node (ref "U6") (pin "27") (pinfunction "PTC6_27") (pintype "bidirectional"))
    )
    (net (code "103") (name "/~{LISA_SS_1.8}") (class "Default")
      (node (ref "LISA1") (pin "SPI_MRDY/GPIO14") (pinfunction "SPI_MRDY/GPIO14_SPI_MRDY/GPIO14") (pintype "bidirectional"))
    )
    (net (code "104") (name "GND") (class "Default")
      (node (ref "ANT_UFL") (pin "GND1") (pinfunction "GND1_GND1") (pintype "bidirectional"))
      (node (ref "ANT_UFL") (pin "GND2") (pinfunction "GND2_GND2") (pintype "bidirectional"))
      (node (ref "ANT_UFL") (pin "GND3") (pinfunction "GND3_GND3") (pintype "bidirectional"))
      (node (ref "C1") (pin "2") (pinfunction "2_2") (pintype "passive"))
      (node (ref "C10") (pin "2") (pinfunction "2_2") (pintype "passive"))
      (node (ref "C11") (pin "2") (pinfunction "2_2") (pintype "passive"))
      (node (ref "C12") (pin "2") (pinfunction "2_2") (pintype "passive"))
      (node (ref "C16") (pin "2") (pinfunction "2_2") (pintype "passive"))
      (node (ref "C17") (pin "2") (pinfunction "2_2") (pintype "passive"))
      (node (ref "C18") (pin "2") (pinfunction "2_2") (pintype "passive"))
      (node (ref "C19") (pin "2") (pinfunction "2_2") (pintype "passive"))
      (node (ref "C2") (pin "2") (pinfunction "2_2") (pintype "passive"))
      (node (ref "C20") (pin "2") (pinfunction "2_2") (pintype "passive"))
      (node (ref "C21") (pin "2") (pinfunction "2_2") (pintype "passive"))
      (node (ref "C22") (pin "2") (pinfunction "2_2") (pintype "passive"))
      (node (ref "C23") (pin "2") (pinfunction "2_2") (pintype "passive"))
      (node (ref "C24") (pin "2") (pinfunction "2_2") (pintype "passive"))
      (node (ref "C25") (pin "2") (pinfunction "2_2") (pintype "passive"))
      (node (ref "C26") (pin "2") (pinfunction "2_2") (pintype "passive"))
      (node (ref "C27") (pin "1") (pinfunction "C1_1") (pintype "passive"))
      (node (ref "C28") (pin "2") (pinfunction "2_2") (pintype "passive"))
      (node (ref "C29") (pin "2") (pinfunction "2_2") (pintype "passive"))
      (node (ref "C3") (pin "2") (pinfunction "2_2") (pintype "passive"))
      (node (ref "C30") (pin "2") (pinfunction "2_2") (pintype "passive"))
      (node (ref "C31") (pin "2") (pinfunction "2_2") (pintype "passive"))
      (node (ref "C32") (pin "2") (pinfunction "2_2") (pintype "passive"))
      (node (ref "C33") (pin "2") (pinfunction "2_2") (pintype "passive"))
      (node (ref "C34") (pin "2") (pinfunction "2_2") (pintype "passive"))
      (node (ref "C35") (pin "2") (pinfunction "2_2") (pintype "passive"))
      (node (ref "C36") (pin "2") (pinfunction "2_2") (pintype "passive"))
      (node (ref "C37") (pin "2") (pinfunction "2_2") (pintype "passive"))
      (node (ref "C38") (pin "2") (pinfunction "2_2") (pintype "passive"))
      (node (ref "C4") (pin "2") (pinfunction "2_2") (pintype "passive"))
      (node (ref "C41") (pin "2") (pinfunction "2_2") (pintype "passive"))
      (node (ref "C42") (pin "2") (pinfunction "2_2") (pintype "passive"))
      (node (ref "C43") (pin "2") (pinfunction "2_2") (pintype "passive"))
      (node (ref "C44") (pin "2") (pinfunction "2_2") (pintype "passive"))
      (node (ref "C45") (pin "2") (pinfunction "2_2") (pintype "passive"))
      (node (ref "C5") (pin "2") (pinfunction "2_2") (pintype "passive"))
      (node (ref "C51") (pin "2") (pinfunction "2_2") (pintype "passive"))
      (node (ref "C57") (pin "P$2") (pinfunction "NEG_P$2") (pintype "bidirectional"))
      (node (ref "C58") (pin "2") (pinfunction "2_2") (pintype "passive"))
      (node (ref "C59") (pin "2") (pinfunction "2_2") (pintype "passive"))
      (node (ref "C6") (pin "1") (pinfunction "1_1") (pintype "passive"))
      (node (ref "C60") (pin "2") (pinfunction "2_2") (pintype "passive"))
      (node (ref "C61") (pin "2") (pinfunction "2_2") (pintype "passive"))
      (node (ref "C7") (pin "2") (pinfunction "2_2") (pintype "passive"))
      (node (ref "C77") (pin "2") (pinfunction "2_2") (pintype "passive"))
      (node (ref "C8") (pin "2") (pinfunction "2_2") (pintype "passive"))
      (node (ref "C9") (pin "2") (pinfunction "2_2") (pintype "passive"))
      (node (ref "J1") (pin "GND") (pinfunction "GND_GND") (pintype "bidirectional"))
      (node (ref "J1") (pin "GND$1") (pinfunction "GND_GND$1") (pintype "bidirectional"))
      (node (ref "J1") (pin "GND$2") (pinfunction "GND_GND$2") (pintype "bidirectional"))
      (node (ref "J1") (pin "GND$3") (pinfunction "GND_GND$3") (pintype "bidirectional"))
      (node (ref "J1") (pin "GND$4") (pinfunction "GND_GND$4") (pintype "bidirectional"))
      (node (ref "J1") (pin "GND$5") (pinfunction "GND_GND$5") (pintype "bidirectional"))
      (node (ref "J1") (pin "GND$6") (pinfunction "GND_GND$6") (pintype "bidirectional"))
      (node (ref "J20") (pin "CHASSIS1") (pinfunction "CHASSIS_1_CHASSIS1") (pintype "bidirectional"))
      (node (ref "J20") (pin "CHASSIS2") (pinfunction "CHASSIS_2_CHASSIS2") (pintype "bidirectional"))
      (node (ref "J20") (pin "GND") (pinfunction "GND_GND") (pintype "bidirectional"))
      (node (ref "J7") (pin "3") (pinfunction "P$3_3") (pintype "bidirectional"))
      (node (ref "J7") (pin "5") (pinfunction "P$5_5") (pintype "bidirectional"))
      (node (ref "J7") (pin "7") (pinfunction "P$7_7") (pintype "bidirectional"))
      (node (ref "J7") (pin "9") (pinfunction "P$9_9") (pintype "bidirectional"))
      (node (ref "J8") (pin "3") (pinfunction "P$3_3") (pintype "bidirectional"))
      (node (ref "J8") (pin "5") (pinfunction "P$5_5") (pintype "bidirectional"))
      (node (ref "J8") (pin "7") (pinfunction "P$7_7") (pintype "bidirectional"))
      (node (ref "J8") (pin "9") (pinfunction "P$9_9") (pintype "bidirectional"))
      (node (ref "JLEFT_A") (pin "5") (pinfunction "5_5") (pintype "passive"))
      (node (ref "JRIGHT_A") (pin "5") (pinfunction "5_5") (pintype "passive"))
      (node (ref "L3") (pin "2") (pinfunction "P$2_2") (pintype "bidirectional"))
      (node (ref "L4") (pin "2") (pinfunction "P$2_2") (pintype "bidirectional"))
      (node (ref "L9") (pin "2") (pinfunction "P$2_2") (pintype "bidirectional"))
      (node (ref "LISA1") (pin "GND$1") (pinfunction "GND$1_GND$1") (pintype "power_in"))
      (node (ref "LISA1") (pin "GND$17") (pinfunction "GND$17_GND$17") (pintype "bidirectional"))
      (node (ref "LISA1") (pin "GND$25") (pinfunction "GND$25_GND$25") (pintype "bidirectional"))
      (node (ref "LISA1") (pin "GND$28") (pinfunction "GND$28_GND$28") (pintype "power_in"))
      (node (ref "LISA1") (pin "GND$29") (pinfunction "GND$29_GND$29") (pintype "power_in"))
      (node (ref "LISA1") (pin "GND$3") (pinfunction "GND$2_GND$3") (pintype "power_in"))
      (node (ref "LISA1") (pin "GND$30") (pinfunction "GND$30_GND$30") (pintype "power_in"))
      (node (ref "LISA1") (pin "GND$31") (pinfunction "GND$31_GND$31") (pintype "power_in"))
      (node (ref "LISA1") (pin "GND$32") (pinfunction "GND$32_GND$32") (pintype "power_in"))
      (node (ref "LISA1") (pin "GND$33") (pinfunction "GND$33_GND$33") (pintype "power_in"))
      (node (ref "LISA1") (pin "GND$34") (pinfunction "GND$34_GND$34") (pintype "power_in"))
      (node (ref "LISA1") (pin "GND$35") (pinfunction "GND$35_GND$35") (pintype "power_in"))
      (node (ref "LISA1") (pin "GND$36") (pinfunction "GND$36_GND$36") (pintype "power_in"))
      (node (ref "LISA1") (pin "GND$37") (pinfunction "GND$37_GND$37") (pintype "power_in"))
      (node (ref "LISA1") (pin "GND$38") (pinfunction "GND$38_GND$38") (pintype "power_in"))
      (node (ref "LISA1") (pin "GND$6") (pinfunction "GND$6_GND$6") (pintype "power_in"))
      (node (ref "LISA1") (pin "GND$60") (pinfunction "GND$60_GND$60") (pintype "power_in"))
      (node (ref "LISA1") (pin "GND$64") (pinfunction "GND$64_GND$64") (pintype "power_in"))
      (node (ref "LISA1") (pin "GND$65") (pinfunction "GND$65_GND$65") (pintype "power_in"))
      (node (ref "LISA1") (pin "GND$66") (pinfunction "GND$66_GND$66") (pintype "power_in"))
      (node (ref "LISA1") (pin "GND$67") (pinfunction "GND$67_GND$67") (pintype "power_in"))
      (node (ref "LISA1") (pin "GND$69") (pinfunction "GND$69_GND$69") (pintype "power_in"))
      (node (ref "LISA1") (pin "GND$7") (pinfunction "GND$7_GND$7") (pintype "power_in"))
      (node (ref "LISA1") (pin "GND$70") (pinfunction "GND$70_GND$70") (pintype "power_in"))
      (node (ref "LISA1") (pin "GND$71") (pinfunction "GND$71_GND$71") (pintype "power_in"))
      (node (ref "LISA1") (pin "GND$72") (pinfunction "GND$72_GND$72") (pintype "power_in"))
      (node (ref "LISA1") (pin "GND$73") (pinfunction "GND$73_GND$73") (pintype "power_in"))
      (node (ref "LISA1") (pin "GND$75") (pinfunction "GND$75_GND$75") (pintype "power_in"))
      (node (ref "LISA1") (pin "GND$8") (pinfunction "GND$8_GND$8") (pintype "power_in"))
      (node (ref "LISA1") (pin "N") (pinfunction "GND$76_N") (pintype "power_in"))
      (node (ref "LISA1") (pin "RSVD") (pinfunction "RSVD_RSVD") (pintype "bidirectional"))
      (node (ref "LISA1") (pin "RTS") (pinfunction "RTS_RTS") (pintype "bidirectional"))
      (node (ref "R2000") (pin "1") (pinfunction "1_1") (pintype "passive"))
      (node (ref "R26") (pin "2") (pinfunction "2_2") (pintype "passive"))
      (node (ref "R28") (pin "1") (pinfunction "1_1") (pintype "passive"))
      (node (ref "R3") (pin "2") (pinfunction "2_2") (pintype "passive"))
      (node (ref "R33") (pin "1") (pinfunction "1_1") (pintype "passive"))
      (node (ref "R41") (pin "2") (pinfunction "2_2") (pintype "passive"))
      (node (ref "R44") (pin "2") (pinfunction "2_2") (pintype "passive"))
      (node (ref "R46") (pin "1") (pinfunction "1_1") (pintype "passive"))
      (node (ref "R50") (pin "2") (pinfunction "2_2") (pintype "passive"))
      (node (ref "R53") (pin "2") (pinfunction "2_2") (pintype "passive"))
      (node (ref "R65") (pin "2") (pinfunction "2_2") (pintype "passive"))
      (node (ref "R68") (pin "2") (pinfunction "2_2") (pintype "passive"))
      (node (ref "R7") (pin "1") (pinfunction "1_1") (pintype "passive"))
      (node (ref "R70") (pin "1") (pinfunction "1_1") (pintype "passive"))
      (node (ref "R8") (pin "1") (pinfunction "1_1") (pintype "passive"))
      (node (ref "R9") (pin "1") (pinfunction "1_1") (pintype "passive"))
      (node (ref "SARA1") (pin "1") (pinfunction "GND$1_1") (pintype "bidirectional"))
      (node (ref "SARA1") (pin "10") (pinfunction "RTS$10_10") (pintype "bidirectional"))
      (node (ref "SARA1") (pin "14") (pinfunction "GND$14_14") (pintype "bidirectional"))
      (node (ref "SARA1") (pin "20") (pinfunction "GND$20_20") (pintype "bidirectional"))
      (node (ref "SARA1") (pin "21") (pinfunction "GND$21_21") (pintype "bidirectional"))
      (node (ref "SARA1") (pin "22") (pinfunction "GND$22_22") (pintype "power_in"))
      (node (ref "SARA1") (pin "3") (pinfunction "GND$3_3") (pintype "bidirectional"))
      (node (ref "SARA1") (pin "30") (pinfunction "GND$30_30") (pintype "bidirectional"))
      (node (ref "SARA1") (pin "32") (pinfunction "GND$32_32") (pintype "power_in"))
      (node (ref "SARA1") (pin "33") (pinfunction "RSVD$33_33") (pintype "power_in"))
      (node (ref "SARA1") (pin "43") (pinfunction "GND$43_43") (pintype "bidirectional"))
      (node (ref "SARA1") (pin "5") (pinfunction "GND$5_5") (pintype "bidirectional"))
      (node (ref "SARA1") (pin "50") (pinfunction "GND$50_50") (pintype "bidirectional"))
      (node (ref "SARA1") (pin "54") (pinfunction "GND$54_54") (pintype "power_in"))
      (node (ref "SARA1") (pin "55") (pinfunction "GND$55_55") (pintype "power_in"))
      (node (ref "SARA1") (pin "57") (pinfunction "GND$57_57") (pintype "power_in"))
      (node (ref "SARA1") (pin "58") (pinfunction "GND$58_58") (pintype "power_in"))
      (node (ref "SARA1") (pin "59") (pinfunction "GND$59_59") (pintype "power_in"))
      (node (ref "SARA1") (pin "60") (pinfunction "GND$60_60") (pintype "power_in"))
      (node (ref "SARA1") (pin "61") (pinfunction "GND$61_61") (pintype "power_in"))
      (node (ref "SARA1") (pin "63") (pinfunction "GND$63_63") (pintype "power_in"))
      (node (ref "SARA1") (pin "64") (pinfunction "GND$64_64") (pintype "power_in"))
      (node (ref "SARA1") (pin "65") (pinfunction "GND$65_65") (pintype "bidirectional"))
      (node (ref "SARA1") (pin "66") (pinfunction "GND$66_66") (pintype "bidirectional"))
      (node (ref "SARA1") (pin "67") (pinfunction "GND$67_67") (pintype "bidirectional"))
      (node (ref "SARA1") (pin "68") (pinfunction "GND$68_68") (pintype "bidirectional"))
      (node (ref "SARA1") (pin "69") (pinfunction "GND$69_69") (pintype "bidirectional"))
      (node (ref "SARA1") (pin "70") (pinfunction "GND$70_70") (pintype "bidirectional"))
      (node (ref "SARA1") (pin "71") (pinfunction "GND$71_71") (pintype "bidirectional"))
      (node (ref "SARA1") (pin "72") (pinfunction "GND$72_72") (pintype "bidirectional"))
      (node (ref "SARA1") (pin "73") (pinfunction "GND$73_73") (pintype "bidirectional"))
      (node (ref "SARA1") (pin "74") (pinfunction "GND$74_74") (pintype "bidirectional"))
      (node (ref "SARA1") (pin "75") (pinfunction "GND$75_75") (pintype "bidirectional"))
      (node (ref "SARA1") (pin "76") (pinfunction "GND$76_76") (pintype "bidirectional"))
      (node (ref "SARA1") (pin "77") (pinfunction "GND$77_77") (pintype "bidirectional"))
      (node (ref "SARA1") (pin "78") (pinfunction "GND$78_78") (pintype "bidirectional"))
      (node (ref "SARA1") (pin "79") (pinfunction "GND$79_79") (pintype "bidirectional"))
      (node (ref "SARA1") (pin "80") (pinfunction "GND$80_80") (pintype "bidirectional"))
      (node (ref "SARA1") (pin "81") (pinfunction "GND$81_81") (pintype "bidirectional"))
      (node (ref "SARA1") (pin "82") (pinfunction "GND$82_82") (pintype "bidirectional"))
      (node (ref "SARA1") (pin "83") (pinfunction "GND$83_83") (pintype "bidirectional"))
      (node (ref "SARA1") (pin "84") (pinfunction "GND$84_84") (pintype "bidirectional"))
      (node (ref "SARA1") (pin "85") (pinfunction "GND$85_85") (pintype "bidirectional"))
      (node (ref "SARA1") (pin "86") (pinfunction "GND$86_86") (pintype "bidirectional"))
      (node (ref "SARA1") (pin "87") (pinfunction "GND$87_87") (pintype "bidirectional"))
      (node (ref "SARA1") (pin "88") (pinfunction "GND$88_88") (pintype "bidirectional"))
      (node (ref "SARA1") (pin "89") (pinfunction "GND$89_89") (pintype "bidirectional"))
      (node (ref "SARA1") (pin "9") (pinfunction "DTR$9_9") (pintype "bidirectional"))
      (node (ref "SARA1") (pin "90") (pinfunction "GND$90_90") (pintype "bidirectional"))
      (node (ref "SARA1") (pin "91") (pinfunction "GND$91_91") (pintype "bidirectional"))
      (node (ref "SARA1") (pin "92") (pinfunction "GND$92_92") (pintype "bidirectional"))
      (node (ref "SARA1") (pin "93") (pinfunction "GND$93_93") (pintype "bidirectional"))
      (node (ref "SARA1") (pin "94") (pinfunction "GND$94_94") (pintype "bidirectional"))
      (node (ref "SARA1") (pin "95") (pinfunction "GND$95_95") (pintype "bidirectional"))
      (node (ref "SARA1") (pin "96") (pinfunction "GND$96_96") (pintype "bidirectional"))
      (node (ref "SIM1") (pin "C5-GND") (pinfunction "GND_C5-GND") (pintype "bidirectional"))
      (node (ref "SW_PGM") (pin "B") (pinfunction "P$2_B") (pintype "bidirectional"))
      (node (ref "SW_PGM") (pin "B2") (pinfunction "P$2_B2") (pintype "bidirectional"))
      (node (ref "SW_SYS_RST") (pin "B") (pinfunction "P$2_B") (pintype "bidirectional"))
      (node (ref "SW_SYS_RST") (pin "B2") (pinfunction "P$2_B2") (pintype "bidirectional"))
      (node (ref "SW_USR_RST") (pin "B") (pinfunction "P$2_B") (pintype "bidirectional"))
      (node (ref "SW_USR_RST") (pin "B2") (pinfunction "P$2_B2") (pintype "bidirectional"))
      (node (ref "T2") (pin "2") (pinfunction "E_2") (pintype "passive"))
      (node (ref "TP18") (pin "TP") (pinfunction "TP_TP") (pintype "input"))
      (node (ref "TP19") (pin "TP") (pinfunction "TP_TP") (pintype "input"))
      (node (ref "TP20") (pin "TP") (pinfunction "TP_TP") (pintype "input"))
      (node (ref "U1") (pin "6") (pinfunction "GND_6") (pintype "bidirectional"))
      (node (ref "U1") (pin "PAD") (pinfunction "GND_PAD") (pintype "bidirectional"))
      (node (ref "U10") (pin "A1") (pinfunction "GND_A1") (pintype "bidirectional"))
      (node (ref "U10") (pin "A2") (pinfunction "GND_A2") (pintype "bidirectional"))
      (node (ref "U10") (pin "B1") (pinfunction "GND_B1") (pintype "bidirectional"))
      (node (ref "U19") (pin "1") (pinfunction "CTG_1") (pintype "bidirectional"))
      (node (ref "U19") (pin "4") (pinfunction "GND_4") (pintype "bidirectional"))
      (node (ref "U19") (pin "6") (pinfunction "QST_6") (pintype "bidirectional"))
      (node (ref "U19") (pin "EP") (pinfunction "GND_EP") (pintype "bidirectional"))
      (node (ref "U2") (pin "2") (pinfunction "GND_2") (pintype "bidirectional"))
      (node (ref "U2") (pin "POWERPAD") (pinfunction "PGND_POWERPAD") (pintype "bidirectional"))
      (node (ref "U3") (pin "4") (pinfunction "VSS_4") (pintype "bidirectional"))
      (node (ref "U3") (pin "P$9") (pinfunction "VSS_P$9") (pintype "bidirectional"))
      (node (ref "U5") (pin "31") (pinfunction "VSS_31") (pintype "bidirectional"))
      (node (ref "U5") (pin "4") (pinfunction "VSS_4") (pintype "bidirectional"))
      (node (ref "U5") (pin "47") (pinfunction "VSS_47") (pintype "bidirectional"))
      (node (ref "U6") (pin "16") (pinfunction "VSS_16") (pintype "bidirectional"))
      (node (ref "U6") (pin "8") (pinfunction "VSSA_8") (pintype "bidirectional"))
      (node (ref "U6") (pin "PAD") (pinfunction "VSS_PAD") (pintype "bidirectional"))
      (node (ref "U7") (pin "3") (pinfunction "P$3_3") (pintype "bidirectional"))
      (node (ref "U8") (pin "P$16") (pinfunction "DIR2_P$16") (pintype "input"))
      (node (ref "U8") (pin "P$6") (pinfunction "DIR4_P$6") (pintype "input"))
      (node (ref "U8") (pin "P$7") (pinfunction "~{OE}_P$7") (pintype "input"))
      (node (ref "U8") (pin "P$8") (pinfunction "GND_P$8") (pintype "passive"))
      (node (ref "U9") (pin "3") (pinfunction "P$3_3") (pintype "bidirectional"))
      (node (ref "X1") (pin "GND") (pinfunction "GND_GND") (pintype "bidirectional"))
    )
    (net (code "105") (name "Net-(C6-Pad2)") (class "Default")
      (node (ref "C6") (pin "2") (pinfunction "2_2") (pintype "passive"))
      (node (ref "R1") (pin "1") (pinfunction "1_1") (pintype "passive"))
      (node (ref "U10") (pin "A3") (pinfunction "VOUT_A3") (pintype "bidirectional"))
      (node (ref "U10") (pin "B3") (pinfunction "VOUT_B3") (pintype "bidirectional"))
      (node (ref "U10") (pin "C3") (pinfunction "VOUT_C3") (pintype "bidirectional"))
    )
    (net (code "106") (name "Net-(C27-C2)") (class "Default")
      (node (ref "C27") (pin "2") (pinfunction "C2_2") (pintype "passive"))
      (node (ref "R4") (pin "2") (pinfunction "2_2") (pintype "passive"))
      (node (ref "U19") (pin "3") (pinfunction "VDD_3") (pintype "bidirectional"))
    )
    (net (code "107") (name "Net-(D1-PadCATHODE)") (class "Default")
      (node (ref "D1") (pin "CATHODE") (pinfunction "CATHODE_CATHODE") (pintype "bidirectional"))
      (node (ref "R26") (pin "1") (pinfunction "1_1") (pintype "passive"))
    )
    (net (code "108") (name "Net-(D2-PadCATHODE)") (class "Default")
      (node (ref "D2") (pin "CATHODE") (pinfunction "CATHODE_CATHODE") (pintype "bidirectional"))
      (node (ref "R43") (pin "1") (pinfunction "1_1") (pintype "passive"))
    )
    (net (code "109") (name "Net-(D3-PadCATHODE)") (class "Default")
      (node (ref "D3") (pin "CATHODE") (pinfunction "CATHODE_CATHODE") (pintype "bidirectional"))
      (node (ref "R3") (pin "1") (pinfunction "1_1") (pintype "passive"))
    )
    (net (code "110") (name "Net-(D5-PadCATHODE)") (class "Default")
      (node (ref "D5") (pin "CATHODE") (pinfunction "CATHODE_CATHODE") (pintype "bidirectional"))
      (node (ref "R41") (pin "1") (pinfunction "1_1") (pintype "passive"))
    )
    (net (code "111") (name "Net-(D6-PadCATHODE)") (class "Default")
      (node (ref "D6") (pin "CATHODE") (pinfunction "CATHODE_CATHODE") (pintype "bidirectional"))
      (node (ref "R68") (pin "1") (pinfunction "1_1") (pintype "passive"))
    )
    (net (code "112") (name "Net-(D7-PadCATHODE)") (class "Default")
      (node (ref "D7") (pin "CATHODE") (pinfunction "CATHODE_CATHODE") (pintype "bidirectional"))
      (node (ref "R65") (pin "1") (pinfunction "1_1") (pintype "passive"))
    )
    (net (code "113") (name "Net-(D8-PadCATHODE)") (class "Default")
      (node (ref "D8") (pin "CATHODE") (pinfunction "CATHODE_CATHODE") (pintype "bidirectional"))
      (node (ref "R44") (pin "1") (pinfunction "1_1") (pintype "passive"))
    )
    (net (code "114") (name "Net-(L1-P$1)") (class "Default")
      (node (ref "C10") (pin "1") (pinfunction "1_1") (pintype "passive"))
      (node (ref "C8") (pin "1") (pinfunction "1_1") (pintype "passive"))
      (node (ref "L1") (pin "1") (pinfunction "P$1_1") (pintype "bidirectional"))
      (node (ref "R16") (pin "2") (pinfunction "2_2") (pintype "passive"))
      (node (ref "U5") (pin "3") (pinfunction "VDD_3") (pintype "bidirectional"))
    )
    (net (code "115") (name "Net-(L1-P$2)") (class "Default")
      (node (ref "C13") (pin "1") (pinfunction "1_1") (pintype "passive"))
      (node (ref "L1") (pin "2") (pinfunction "P$2_2") (pintype "bidirectional"))
      (node (ref "R19") (pin "1") (pinfunction "1_1") (pintype "passive"))
      (node (ref "U5") (pin "13") (pinfunction "VDDA_13") (pintype "bidirectional"))
    )
    (net (code "116") (name "Net-(L2-P$2)") (class "Default")
      (node (ref "L2") (pin "2") (pinfunction "P$2_2") (pintype "bidirectional"))
      (node (ref "U4") (pin "1") (pinfunction "A1_1") (pintype "bidirectional"))
      (node (ref "U4") (pin "2") (pinfunction "A2_2") (pintype "bidirectional"))
    )
    (net (code "117") (name "Net-(L5-PadP$1)") (class "Default")
      (node (ref "L5") (pin "P$1") (pinfunction "P$1_P$1") (pintype "bidirectional"))
      (node (ref "U2") (pin "8") (pinfunction "L1_8") (pintype "bidirectional"))
      (node (ref "U2") (pin "9") (pinfunction "L1_9") (pintype "bidirectional"))
    )
    (net (code "118") (name "Net-(L5-PadP$2)") (class "Default")
      (node (ref "L5") (pin "P$2") (pinfunction "P$2_P$2") (pintype "bidirectional"))
      (node (ref "U2") (pin "6") (pinfunction "L2_6") (pintype "bidirectional"))
      (node (ref "U2") (pin "7") (pinfunction "L2_7") (pintype "bidirectional"))
    )
    (net (code "119") (name "Net-(LISA1-PadDTR)") (class "Default")
      (node (ref "LISA1") (pin "DTR") (pinfunction "DTR_DTR") (pintype "bidirectional"))
      (node (ref "R50") (pin "1") (pinfunction "1_1") (pintype "passive"))
    )
    (net (code "120") (name "Net-(R67-Pad1)") (class "Default")
      (node (ref "R67") (pin "1") (pinfunction "1_1") (pintype "passive"))
      (node (ref "R69") (pin "2") (pinfunction "2_2") (pintype "passive"))
      (node (ref "U2") (pin "4") (pinfunction "VOUT_4") (pintype "bidirectional"))
      (node (ref "U2") (pin "5") (pinfunction "VOUT_5") (pintype "bidirectional"))
    )
    (net (code "121") (name "Net-(T2-B)") (class "Default")
      (node (ref "R52") (pin "2") (pinfunction "2_2") (pintype "passive"))
      (node (ref "R53") (pin "1") (pinfunction "1_1") (pintype "passive"))
      (node (ref "T2") (pin "1") (pinfunction "B_1") (pintype "passive"))
    )
    (net (code "122") (name "Net-(T2-C)") (class "Default")
      (node (ref "R43") (pin "2") (pinfunction "2_2") (pintype "passive"))
      (node (ref "T2") (pin "3") (pinfunction "C_3") (pintype "passive"))
    )
    (net (code "123") (name "Net-(U1-IAC)") (class "Default")
      (node (ref "R8") (pin "2") (pinfunction "2_2") (pintype "passive"))
      (node (ref "U1") (pin "16") (pinfunction "IAC_16") (pintype "bidirectional"))
    )
    (net (code "124") (name "Net-(U1-IEND)") (class "Default")
      (node (ref "R9") (pin "2") (pinfunction "2_2") (pintype "passive"))
      (node (ref "U1") (pin "13") (pinfunction "IEND_13") (pintype "bidirectional"))
    )
    (net (code "125") (name "Net-(U1-ISEL)") (class "Default")
      (node (ref "J2") (pin "3") (pinfunction "3_3") (pintype "bidirectional"))
      (node (ref "R15") (pin "2") (pinfunction "2_2") (pintype "passive"))
      (node (ref "R6") (pin "2") (pinfunction "2_2") (pintype "passive"))
      (node (ref "U1") (pin "1") (pinfunction "VIN_1") (pintype "bidirectional"))
      (node (ref "U1") (pin "2") (pinfunction "VINSNS_2") (pintype "bidirectional"))
      (node (ref "U1") (pin "9") (pinfunction "ISEL_9") (pintype "bidirectional"))
    )
    (net (code "126") (name "Net-(U1-IUSB)") (class "Default")
      (node (ref "R7") (pin "2") (pinfunction "2_2") (pintype "passive"))
      (node (ref "U1") (pin "15") (pinfunction "IUSB_15") (pintype "bidirectional"))
    )
    (net (code "127") (name "Net-(U1-MODE)") (class "Default")
      (node (ref "R15") (pin "1") (pinfunction "1_1") (pintype "passive"))
      (node (ref "R28") (pin "2") (pinfunction "2_2") (pintype "passive"))
      (node (ref "U1") (pin "14") (pinfunction "MODE_14") (pintype "bidirectional"))
    )
    (net (code "128") (name "Net-(U1-SD)") (class "Default")
      (node (ref "R46") (pin "2") (pinfunction "2_2") (pintype "passive"))
      (node (ref "U1") (pin "7") (pinfunction "SD_7") (pintype "bidirectional"))
    )
    (net (code "129") (name "Net-(U1-TH)") (class "Default")
      (node (ref "R10") (pin "1") (pinfunction "1_1") (pintype "passive"))
      (node (ref "R2000") (pin "2") (pinfunction "2_2") (pintype "passive"))
      (node (ref "U1") (pin "8") (pinfunction "TH_8") (pintype "bidirectional"))
    )
    (net (code "130") (name "Net-(U1-TPRG)") (class "Default")
      (node (ref "C22") (pin "1") (pinfunction "1_1") (pintype "passive"))
      (node (ref "U1") (pin "5") (pinfunction "TPRG_5") (pintype "bidirectional"))
    )
    (net (code "131") (name "Net-(U1-VREF)") (class "Default")
      (node (ref "C5") (pin "1") (pinfunction "1_1") (pintype "passive"))
      (node (ref "R10") (pin "2") (pinfunction "2_2") (pintype "passive"))
      (node (ref "U1") (pin "12") (pinfunction "VREF_12") (pintype "bidirectional"))
    )
    (net (code "132") (name "Net-(U2-EN)") (class "Default")
      (node (ref "C16") (pin "1") (pinfunction "1_1") (pintype "passive"))
      (node (ref "R25") (pin "1") (pinfunction "1_1") (pintype "passive"))
      (node (ref "U2") (pin "1") (pinfunction "VINA_1") (pintype "bidirectional"))
      (node (ref "U2") (pin "12") (pinfunction "EN_12") (pintype "bidirectional"))
    )
    (net (code "133") (name "Net-(U2-FB)") (class "Default")
      (node (ref "R69") (pin "1") (pinfunction "1_1") (pintype "passive"))
      (node (ref "R70") (pin "2") (pinfunction "2_2") (pintype "passive"))
      (node (ref "U2") (pin "3") (pinfunction "FB_3") (pintype "bidirectional"))
    )
    (net (code "134") (name "Net-(U2-PS{slash}SYNC)") (class "Default")
      (node (ref "R25") (pin "2") (pinfunction "2_2") (pintype "passive"))
      (node (ref "U2") (pin "13") (pinfunction "PS/SYNC_13") (pintype "bidirectional"))
    )
    (net (code "135") (name "Net-(U3-VDD)") (class "Default")
      (node (ref "C19") (pin "1") (pinfunction "1_1") (pintype "passive"))
      (node (ref "R2") (pin "1") (pinfunction "1_1") (pintype "passive"))
      (node (ref "U3") (pin "3") (pinfunction "~{WP}_3") (pintype "bidirectional"))
      (node (ref "U3") (pin "7") (pinfunction "~{HOLD}_7") (pintype "bidirectional"))
      (node (ref "U3") (pin "8") (pinfunction "VDD_8") (pintype "bidirectional"))
    )
    (net (code "136") (name "Net-(U4-C)") (class "Default")
      (node (ref "C18") (pin "1") (pinfunction "1_1") (pintype "passive"))
      (node (ref "U4") (pin "3") (pinfunction "C_3") (pintype "bidirectional"))
      (node (ref "U5") (pin "8") (pinfunction "VREGIN_8") (pintype "bidirectional"))
    )
    (net (code "137") (name "Net-(U5-EXTAL32)") (class "Default")
      (node (ref "C17") (pin "1") (pinfunction "1_1") (pintype "passive"))
      (node (ref "R38") (pin "1") (pinfunction "1_1") (pintype "passive"))
      (node (ref "U5") (pin "20") (pinfunction "EXTAL32_20") (pintype "bidirectional"))
      (node (ref "X2") (pin "P$1") (pinfunction "XTAL1_P$1") (pintype "bidirectional"))
    )
    (net (code "138") (name "Net-(U5-PTA18)") (class "Default")
      (node (ref "C30") (pin "1") (pinfunction "1_1") (pintype "passive"))
      (node (ref "R5") (pin "2") (pinfunction "2_2") (pintype "passive"))
      (node (ref "U5") (pin "32") (pinfunction "PTA18_32") (pintype "bidirectional"))
      (node (ref "X1") (pin "XTAL1") (pinfunction "XTAL1_XTAL1") (pintype "bidirectional"))
    )
    (net (code "139") (name "Net-(U5-PTA19)") (class "Default")
      (node (ref "C31") (pin "1") (pinfunction "1_1") (pintype "passive"))
      (node (ref "R5") (pin "1") (pinfunction "1_1") (pintype "passive"))
      (node (ref "U5") (pin "33") (pinfunction "PTA19_33") (pintype "bidirectional"))
      (node (ref "X1") (pin "XTAL2") (pinfunction "XTAL2_XTAL2") (pintype "bidirectional"))
    )
    (net (code "140") (name "Net-(U5-PTB19)") (class "Default")
      (node (ref "D1") (pin "ANODE") (pinfunction "ANODE_ANODE") (pintype "bidirectional"))
      (node (ref "U5") (pin "42") (pinfunction "PTB19_42") (pintype "bidirectional"))
    )
    (net (code "141") (name "Net-(U5-VBAT)") (class "Default")
      (node (ref "C9") (pin "1") (pinfunction "1_1") (pintype "passive"))
      (node (ref "R21") (pin "2") (pinfunction "2_2") (pintype "passive"))
      (node (ref "U5") (pin "21") (pinfunction "VBAT_21") (pintype "bidirectional"))
    )
    (net (code "142") (name "Net-(U5-VDD1)") (class "Default")
      (node (ref "C7") (pin "1") (pinfunction "1_1") (pintype "passive"))
      (node (ref "R17") (pin "2") (pinfunction "2_2") (pintype "passive"))
      (node (ref "U5") (pin "30") (pinfunction "VDD1_30") (pintype "bidirectional"))
    )
    (net (code "143") (name "Net-(U5-VDD2)") (class "Default")
      (node (ref "C4") (pin "1") (pinfunction "1_1") (pintype "passive"))
      (node (ref "R18") (pin "2") (pinfunction "2_2") (pintype "passive"))
      (node (ref "U5") (pin "48") (pinfunction "VDD2_48") (pintype "bidirectional"))
    )
    (net (code "144") (name "Net-(U5-VOUT33)") (class "Default")
      (node (ref "R20") (pin "2") (pinfunction "2_2") (pintype "passive"))
      (node (ref "U5") (pin "7") (pinfunction "VOUT33_7") (pintype "bidirectional"))
    )
    (net (code "145") (name "Net-(U5-VREF_OUT)") (class "Default")
      (node (ref "C15") (pin "1") (pinfunction "1_1") (pintype "passive"))
      (node (ref "U5") (pin "17") (pinfunction "VREF_OUT_17") (pintype "bidirectional"))
    )
    (net (code "146") (name "Net-(U5-XTAL32)") (class "Default")
      (node (ref "C23") (pin "1") (pinfunction "1_1") (pintype "passive"))
      (node (ref "R38") (pin "2") (pinfunction "2_2") (pintype "passive"))
      (node (ref "U5") (pin "19") (pinfunction "XTAL32_19") (pintype "bidirectional"))
      (node (ref "X2") (pin "P$2") (pinfunction "XTAL2_P$2") (pintype "bidirectional"))
    )
    (net (code "147") (name "Net-(U6-PTA18)") (class "Default")
      (node (ref "C29") (pin "1") (pinfunction "1_1") (pintype "passive"))
      (node (ref "R39") (pin "2") (pinfunction "2_2") (pintype "passive"))
      (node (ref "U6") (pin "17") (pinfunction "PTA18_17") (pintype "bidirectional"))
      (node (ref "X3") (pin "P$2") (pinfunction "XTAL2_P$2") (pintype "bidirectional"))
    )
    (net (code "148") (name "Net-(U6-PTA19)") (class "Default")
      (node (ref "C32") (pin "1") (pinfunction "1_1") (pintype "passive"))
      (node (ref "R39") (pin "1") (pinfunction "1_1") (pintype "passive"))
      (node (ref "U6") (pin "18") (pinfunction "PTA19_18") (pintype "bidirectional"))
      (node (ref "X3") (pin "P$1") (pinfunction "XTAL1_P$1") (pintype "bidirectional"))
    )
    (net (code "149") (name "Net-(U6-PTB0)") (class "Default")
      (node (ref "R58") (pin "1") (pinfunction "1_1") (pintype "passive"))
      (node (ref "U6") (pin "20") (pinfunction "PTB0_20") (pintype "bidirectional"))
    )
    (net (code "150") (name "Net-(U6-PTB1)") (class "Default")
      (node (ref "R59") (pin "1") (pinfunction "1_1") (pintype "passive"))
      (node (ref "U6") (pin "21") (pinfunction "PTB1_21") (pintype "bidirectional"))
    )
    (net (code "151") (name "Net-(U6-PTC1)") (class "Default")
      (node (ref "R14") (pin "1") (pinfunction "1_1") (pintype "passive"))
      (node (ref "U6") (pin "22") (pinfunction "PTC1_22") (pintype "bidirectional"))
    )
    (net (code "152") (name "Net-(U6-PTC3)") (class "Default")
      (node (ref "R61") (pin "2") (pinfunction "2_2") (pintype "passive"))
      (node (ref "U6") (pin "24") (pinfunction "PTC3_24") (pintype "bidirectional"))
    )
    (net (code "153") (name "Net-(U6-PTC4)") (class "Default")
      (node (ref "R62") (pin "2") (pinfunction "2_2") (pintype "passive"))
      (node (ref "U6") (pin "25") (pinfunction "PTC4_25") (pintype "bidirectional"))
    )
    (net (code "154") (name "Net-(U6-PTC5)") (class "Default")
      (node (ref "R22") (pin "1") (pinfunction "1_1") (pintype "passive"))
      (node (ref "U6") (pin "26") (pinfunction "PTC5_26") (pintype "bidirectional"))
    )
    (net (code "155") (name "Net-(U6-PTD6)") (class "Default")
      (node (ref "R63") (pin "2") (pinfunction "2_2") (pintype "passive"))
      (node (ref "U6") (pin "31") (pinfunction "PTD6_31") (pintype "bidirectional"))
    )
    (net (code "156") (name "Net-(U6-PTD7)") (class "Default")
      (node (ref "R64") (pin "2") (pinfunction "2_2") (pintype "passive"))
      (node (ref "U6") (pin "32") (pinfunction "PTD7_32") (pintype "bidirectional"))
    )
    (net (code "157") (name "Net-(U6-PTE16)") (class "Default")
      (node (ref "R55") (pin "1") (pinfunction "1_1") (pintype "passive"))
      (node (ref "U6") (pin "3") (pinfunction "PTE16_3") (pintype "bidirectional"))
    )
    (net (code "158") (name "Net-(U6-PTE17)") (class "Default")
      (node (ref "R54") (pin "1") (pinfunction "1_1") (pintype "passive"))
      (node (ref "U6") (pin "4") (pinfunction "PTE17_4") (pintype "bidirectional"))
    )
    (net (code "159") (name "Net-(U6-PTE18)") (class "Default")
      (node (ref "R57") (pin "1") (pinfunction "1_1") (pintype "passive"))
      (node (ref "U6") (pin "5") (pinfunction "PTE18_5") (pintype "bidirectional"))
    )
    (net (code "160") (name "Net-(U6-PTE19)") (class "Default")
      (node (ref "R56") (pin "1") (pinfunction "1_1") (pintype "passive"))
      (node (ref "U6") (pin "6") (pinfunction "PTE19_6") (pintype "bidirectional"))
    )
    (net (code "161") (name "Net-(U6-VDD)") (class "Default")
      (node (ref "C28") (pin "1") (pinfunction "1_1") (pintype "passive"))
      (node (ref "C3") (pin "1") (pinfunction "1_1") (pintype "passive"))
      (node (ref "R60") (pin "2") (pinfunction "2_2") (pintype "passive"))
      (node (ref "U6") (pin "15") (pinfunction "VDD_15") (pintype "bidirectional"))
      (node (ref "U6") (pin "7") (pinfunction "VDDA_7") (pintype "bidirectional"))
    )
    (net (code "162") (name "Net-(U8-DIR1)") (class "Default")
      (node (ref "C26") (pin "1") (pinfunction "1_1") (pintype "passive"))
      (node (ref "R48") (pin "2") (pinfunction "2_2") (pintype "passive"))
      (node (ref "U8") (pin "P$14") (pinfunction "VCCA_P$14") (pintype "power_in"))
      (node (ref "U8") (pin "P$15") (pinfunction "DIR1_P$15") (pintype "input"))
      (node (ref "U8") (pin "P$5") (pinfunction "DIR3_P$5") (pintype "input"))
    )
    (net (code "163") (name "Net-(U8-VCCB)") (class "Default")
      (node (ref "C25") (pin "1") (pinfunction "1_1") (pintype "passive"))
      (node (ref "R49") (pin "2") (pinfunction "2_2") (pintype "passive"))
      (node (ref "U8") (pin "P$13") (pinfunction "VCCB_P$13") (pintype "power_in"))
    )
    (net (code "164") (name "Net-(U10-EN)") (class "Default")
      (node (ref "R11") (pin "2") (pinfunction "2_2") (pintype "passive"))
      (node (ref "U10") (pin "B2") (pinfunction "EN_B2") (pintype "bidirectional"))
    )
    (net (code "165") (name "Net-(U19-CELL)") (class "Default")
      (node (ref "C20") (pin "1") (pinfunction "1_1") (pintype "passive"))
      (node (ref "R45") (pin "1") (pinfunction "1_1") (pintype "passive"))
      (node (ref "U19") (pin "2") (pinfunction "CELL_2") (pintype "bidirectional"))
    )
    (net (code "166") (name "unconnected-(LISA1-PadCTS)") (class "Default")
      (node (ref "LISA1") (pin "CTS") (pinfunction "CTS_CTS") (pintype "bidirectional"))
    )
    (net (code "167") (name "unconnected-(LISA1-PadDCD)") (class "Default")
      (node (ref "LISA1") (pin "DCD") (pinfunction "DCD_DCD") (pintype "bidirectional"))
    )
    (net (code "168") (name "unconnected-(LISA1-PadDSR)") (class "Default")
      (node (ref "LISA1") (pin "DSR") (pinfunction "DSR_DSR") (pintype "bidirectional"))
    )
    (net (code "169") (name "unconnected-(LISA1-PadGPIO5)") (class "Default")
      (node (ref "LISA1") (pin "GPIO5") (pinfunction "GPIO5_GPIO5") (pintype "bidirectional"))
    )
    (net (code "170") (name "unconnected-(LISA1-PadGPIO6{slash}I2S1_RXD)") (class "Default")
      (node (ref "LISA1") (pin "GPIO6/I2S1_RXD") (pinfunction "GPIO6/I2S1_RXD_GPIO6/I2S1_RXD") (pintype "bidirectional"))
    )
    (net (code "171") (name "unconnected-(LISA1-PadGPIO7{slash}I2S1_TXD)") (class "Default")
      (node (ref "LISA1") (pin "GPIO7/I2S1_TXD") (pinfunction "GPIO7/I2S1_TXD_GPIO7/I2S1_TXD") (pintype "bidirectional"))
    )
    (net (code "172") (name "unconnected-(LISA1-PadGPIO8{slash}I2S1_CLK)") (class "Default")
      (node (ref "LISA1") (pin "GPIO8/I2S1_CLK") (pinfunction "GPIO8/I2S1_CLK_GPIO8/I2S1_CLK") (pintype "bidirectional"))
    )
    (net (code "173") (name "unconnected-(LISA1-PadGPIO9{slash}I2S1_WA)") (class "Default")
      (node (ref "LISA1") (pin "GPIO9/I2S1_WA") (pinfunction "GPIO9/I2S1_WA_GPIO9/I2S1_WA") (pintype "bidirectional"))
    )
    (net (code "174") (name "unconnected-(LISA1-PadRI)") (class "Default")
      (node (ref "LISA1") (pin "RI") (pinfunction "RI_RI") (pintype "bidirectional"))
    )
    (net (code "175") (name "unconnected-(LISA1-PadRSVD{slash}ANT_DIV)") (class "Default")
      (node (ref "LISA1") (pin "RSVD/ANT_DIV") (pinfunction "RSVD/ANT_DIV_RSVD/ANT_DIV") (pintype "bidirectional"))
    )
    (net (code "176") (name "unconnected-(LISA1-PadRSVD{slash}CODEC_CLK)") (class "Default")
      (node (ref "LISA1") (pin "RSVD/CODEC_CLK") (pinfunction "RSVD/CODEC_CLK_RSVD/CODEC_CLK") (pintype "bidirectional"))
    )
    (net (code "177") (name "unconnected-(LISA1-PadRSVD{slash}I2S_CLK)") (class "Default")
      (node (ref "LISA1") (pin "RSVD/I2S_CLK") (pinfunction "RSVD/I2S_CLK_RSVD/I2S_CLK") (pintype "bidirectional"))
    )
    (net (code "178") (name "unconnected-(LISA1-PadRSVD{slash}I2S_RXD)") (class "Default")
      (node (ref "LISA1") (pin "RSVD/I2S_RXD") (pinfunction "RSVD/I2S_RXD_RSVD/I2S_RXD") (pintype "bidirectional"))
    )
    (net (code "179") (name "unconnected-(LISA1-PadRSVD{slash}I2S_WA)") (class "Default")
      (node (ref "LISA1") (pin "RSVD/I2S_WA") (pinfunction "RSVD/I2S_WA_RSVD/I2S_WA") (pintype "bidirectional"))
    )
    (net (code "180") (name "unconnected-(LISA1-RSVD{slash}IS2_TXD-PadRSVD{slash}I2S_TXD)") (class "Default")
      (node (ref "LISA1") (pin "RSVD/I2S_TXD") (pinfunction "RSVD/IS2_TXD_RSVD/I2S_TXD") (pintype "bidirectional"))
    )
    (net (code "181") (name "unconnected-(R30-Pad2)") (class "Default")
      (node (ref "R30") (pin "2") (pinfunction "2_2") (pintype "passive"))
    )
    (net (code "182") (name "unconnected-(R31-Pad2)") (class "Default")
      (node (ref "R31") (pin "2") (pinfunction "2_2") (pintype "passive"))
    )
    (net (code "183") (name "unconnected-(R32-Pad2)") (class "Default")
      (node (ref "R32") (pin "2") (pinfunction "2_2") (pintype "passive"))
    )
    (net (code "184") (name "unconnected-(R33-Pad2)") (class "Default")
      (node (ref "R33") (pin "2") (pinfunction "2_2") (pintype "passive"))
    )
    (net (code "185") (name "unconnected-(R36-Pad1)") (class "Default")
      (node (ref "R36") (pin "1") (pinfunction "1_1") (pintype "passive"))
    )
    (net (code "186") (name "unconnected-(R37-Pad1)") (class "Default")
      (node (ref "R37") (pin "1") (pinfunction "1_1") (pintype "passive"))
    )
    (net (code "187") (name "unconnected-(SARA1-CODEC_CLK$19-Pad19)") (class "Default")
      (node (ref "SARA1") (pin "19") (pinfunction "CODEC_CLK$19_19") (pintype "bidirectional"))
    )
    (net (code "188") (name "unconnected-(SARA1-CTS$11-Pad11)") (class "Default")
      (node (ref "SARA1") (pin "11") (pinfunction "CTS$11_11") (pintype "bidirectional"))
    )
    (net (code "189") (name "unconnected-(SARA1-DCD$8-Pad8)") (class "Default")
      (node (ref "SARA1") (pin "8") (pinfunction "DCD$8_8") (pintype "bidirectional"))
    )
    (net (code "190") (name "unconnected-(SARA1-DSR$6-Pad6)") (class "Default")
      (node (ref "SARA1") (pin "6") (pinfunction "DSR$6_6") (pintype "bidirectional"))
    )
    (net (code "191") (name "unconnected-(SARA1-GPIO3$24-Pad24)") (class "Default")
      (node (ref "SARA1") (pin "24") (pinfunction "GPIO3$24_24") (pintype "bidirectional"))
    )
    (net (code "192") (name "unconnected-(SARA1-I2S_CLK$36-Pad36)") (class "Default")
      (node (ref "SARA1") (pin "36") (pinfunction "I2S_CLK$36_36") (pintype "bidirectional"))
    )
    (net (code "193") (name "unconnected-(SARA1-I2S_RXD$37-Pad37)") (class "Default")
      (node (ref "SARA1") (pin "37") (pinfunction "I2S_RXD$37_37") (pintype "bidirectional"))
    )
    (net (code "194") (name "unconnected-(SARA1-RI$7-Pad7)") (class "Default")
      (node (ref "SARA1") (pin "7") (pinfunction "RI$7_7") (pintype "bidirectional"))
    )
    (net (code "195") (name "unconnected-(SARA1-RSVD$44-Pad44)") (class "Default")
      (node (ref "SARA1") (pin "44") (pinfunction "RSVD$44_44") (pintype "bidirectional"))
    )
    (net (code "196") (name "unconnected-(SARA1-RSVD$45-Pad45)") (class "Default")
      (node (ref "SARA1") (pin "45") (pinfunction "RSVD$45_45") (pintype "bidirectional"))
    )
    (net (code "197") (name "unconnected-(SARA1-RSVD$46-Pad46)") (class "Default")
      (node (ref "SARA1") (pin "46") (pinfunction "RSVD$46_46") (pintype "bidirectional"))
    )
    (net (code "198") (name "unconnected-(SARA1-RSVD$47-Pad47)") (class "Default")
      (node (ref "SARA1") (pin "47") (pinfunction "RSVD$47_47") (pintype "bidirectional"))
    )
    (net (code "199") (name "unconnected-(SARA1-RSVD$48-Pad48)") (class "Default")
      (node (ref "SARA1") (pin "48") (pinfunction "RSVD$48_48") (pintype "bidirectional"))
    )
    (net (code "200") (name "unconnected-(SARA1-RSVD$49-Pad49)") (class "Default")
      (node (ref "SARA1") (pin "49") (pinfunction "RSVD$49_49") (pintype "bidirectional"))
    )
    (net (code "201") (name "unconnected-(SARA1-SIM_DET$42-Pad42)") (class "Default")
      (node (ref "SARA1") (pin "42") (pinfunction "SIM_DET$42_42") (pintype "bidirectional"))
    )
    (net (code "202") (name "unconnected-(SIM1-NC1-PadMTG1)") (class "Default")
      (node (ref "SIM1") (pin "MTG1") (pinfunction "NC1_MTG1") (pintype "bidirectional"))
    )
    (net (code "203") (name "unconnected-(SIM1-NC2-PadMTG2)") (class "Default")
      (node (ref "SIM1") (pin "MTG2") (pinfunction "NC2_MTG2") (pintype "bidirectional"))
    )
    (net (code "204") (name "unconnected-(U5-PGA0_DP-Pad9)") (class "Default")
      (node (ref "U5") (pin "9") (pinfunction "PGA0_DP_9") (pintype "bidirectional"))
    )
    (net (code "205") (name "unconnected-(U5-PGA1_DM-Pad12)") (class "Default")
      (node (ref "U5") (pin "12") (pinfunction "PGA1_DM_12") (pintype "bidirectional"))
    )
    (net (code "206") (name "unconnected-(U5-PTC6-Pad51)") (class "Default")
      (node (ref "U5") (pin "51") (pinfunction "PTC6_51") (pintype "bidirectional"))
    )
    (net (code "207") (name "unconnected-(U5-PTC7-Pad52)") (class "Default")
      (node (ref "U5") (pin "52") (pinfunction "PTC7_52") (pintype "bidirectional"))
    )
    (net (code "208") (name "unconnected-(U5-PTC10-Pad55)") (class "Default")
      (node (ref "U5") (pin "55") (pinfunction "PTC10_55") (pintype "bidirectional"))
    )
    (net (code "209") (name "unconnected-(U5-PTC11-Pad56)") (class "Default")
      (node (ref "U5") (pin "56") (pinfunction "PTC11_56") (pintype "bidirectional"))
    )
    (net (code "210") (name "unconnected-(U5-PTD0-Pad57)") (class "Default")
      (node (ref "U5") (pin "57") (pinfunction "PTD0_57") (pintype "bidirectional"))
    )
    (net (code "211") (name "unconnected-(U6-DAC0_OUT_PTE_30-Pad9)") (class "Default")
      (node (ref "U6") (pin "9") (pinfunction "DAC0_OUT_PTE_30_9") (pintype "bidirectional"))
    )
    (net (code "212") (name "unconnected-(U6-PTA4-Pad14)") (class "Default")
      (node (ref "U6") (pin "14") (pinfunction "PTA4_14") (pintype "bidirectional"))
    )
    (net (code "213") (name "unconnected-(U8-A3-PadP$3)") (class "Default")
      (node (ref "U8") (pin "P$3") (pinfunction "A3_P$3") (pintype "bidirectional"))
    )
    (net (code "214") (name "unconnected-(U8-A4-PadP$4)") (class "Default")
      (node (ref "U8") (pin "P$4") (pinfunction "A4_P$4") (pintype "bidirectional"))
    )
    (net (code "215") (name "unconnected-(U8-B3-PadP$10)") (class "Default")
      (node (ref "U8") (pin "P$10") (pinfunction "B3_P$10") (pintype "bidirectional"))
    )
    (net (code "216") (name "unconnected-(U8-B4-PadP$9)") (class "Default")
      (node (ref "U8") (pin "P$9") (pinfunction "B4_P$9") (pintype "bidirectional"))
    )
  )
)
